# SteppyMk2.net
KiCad netlist of a schematic drawn in EAGLE
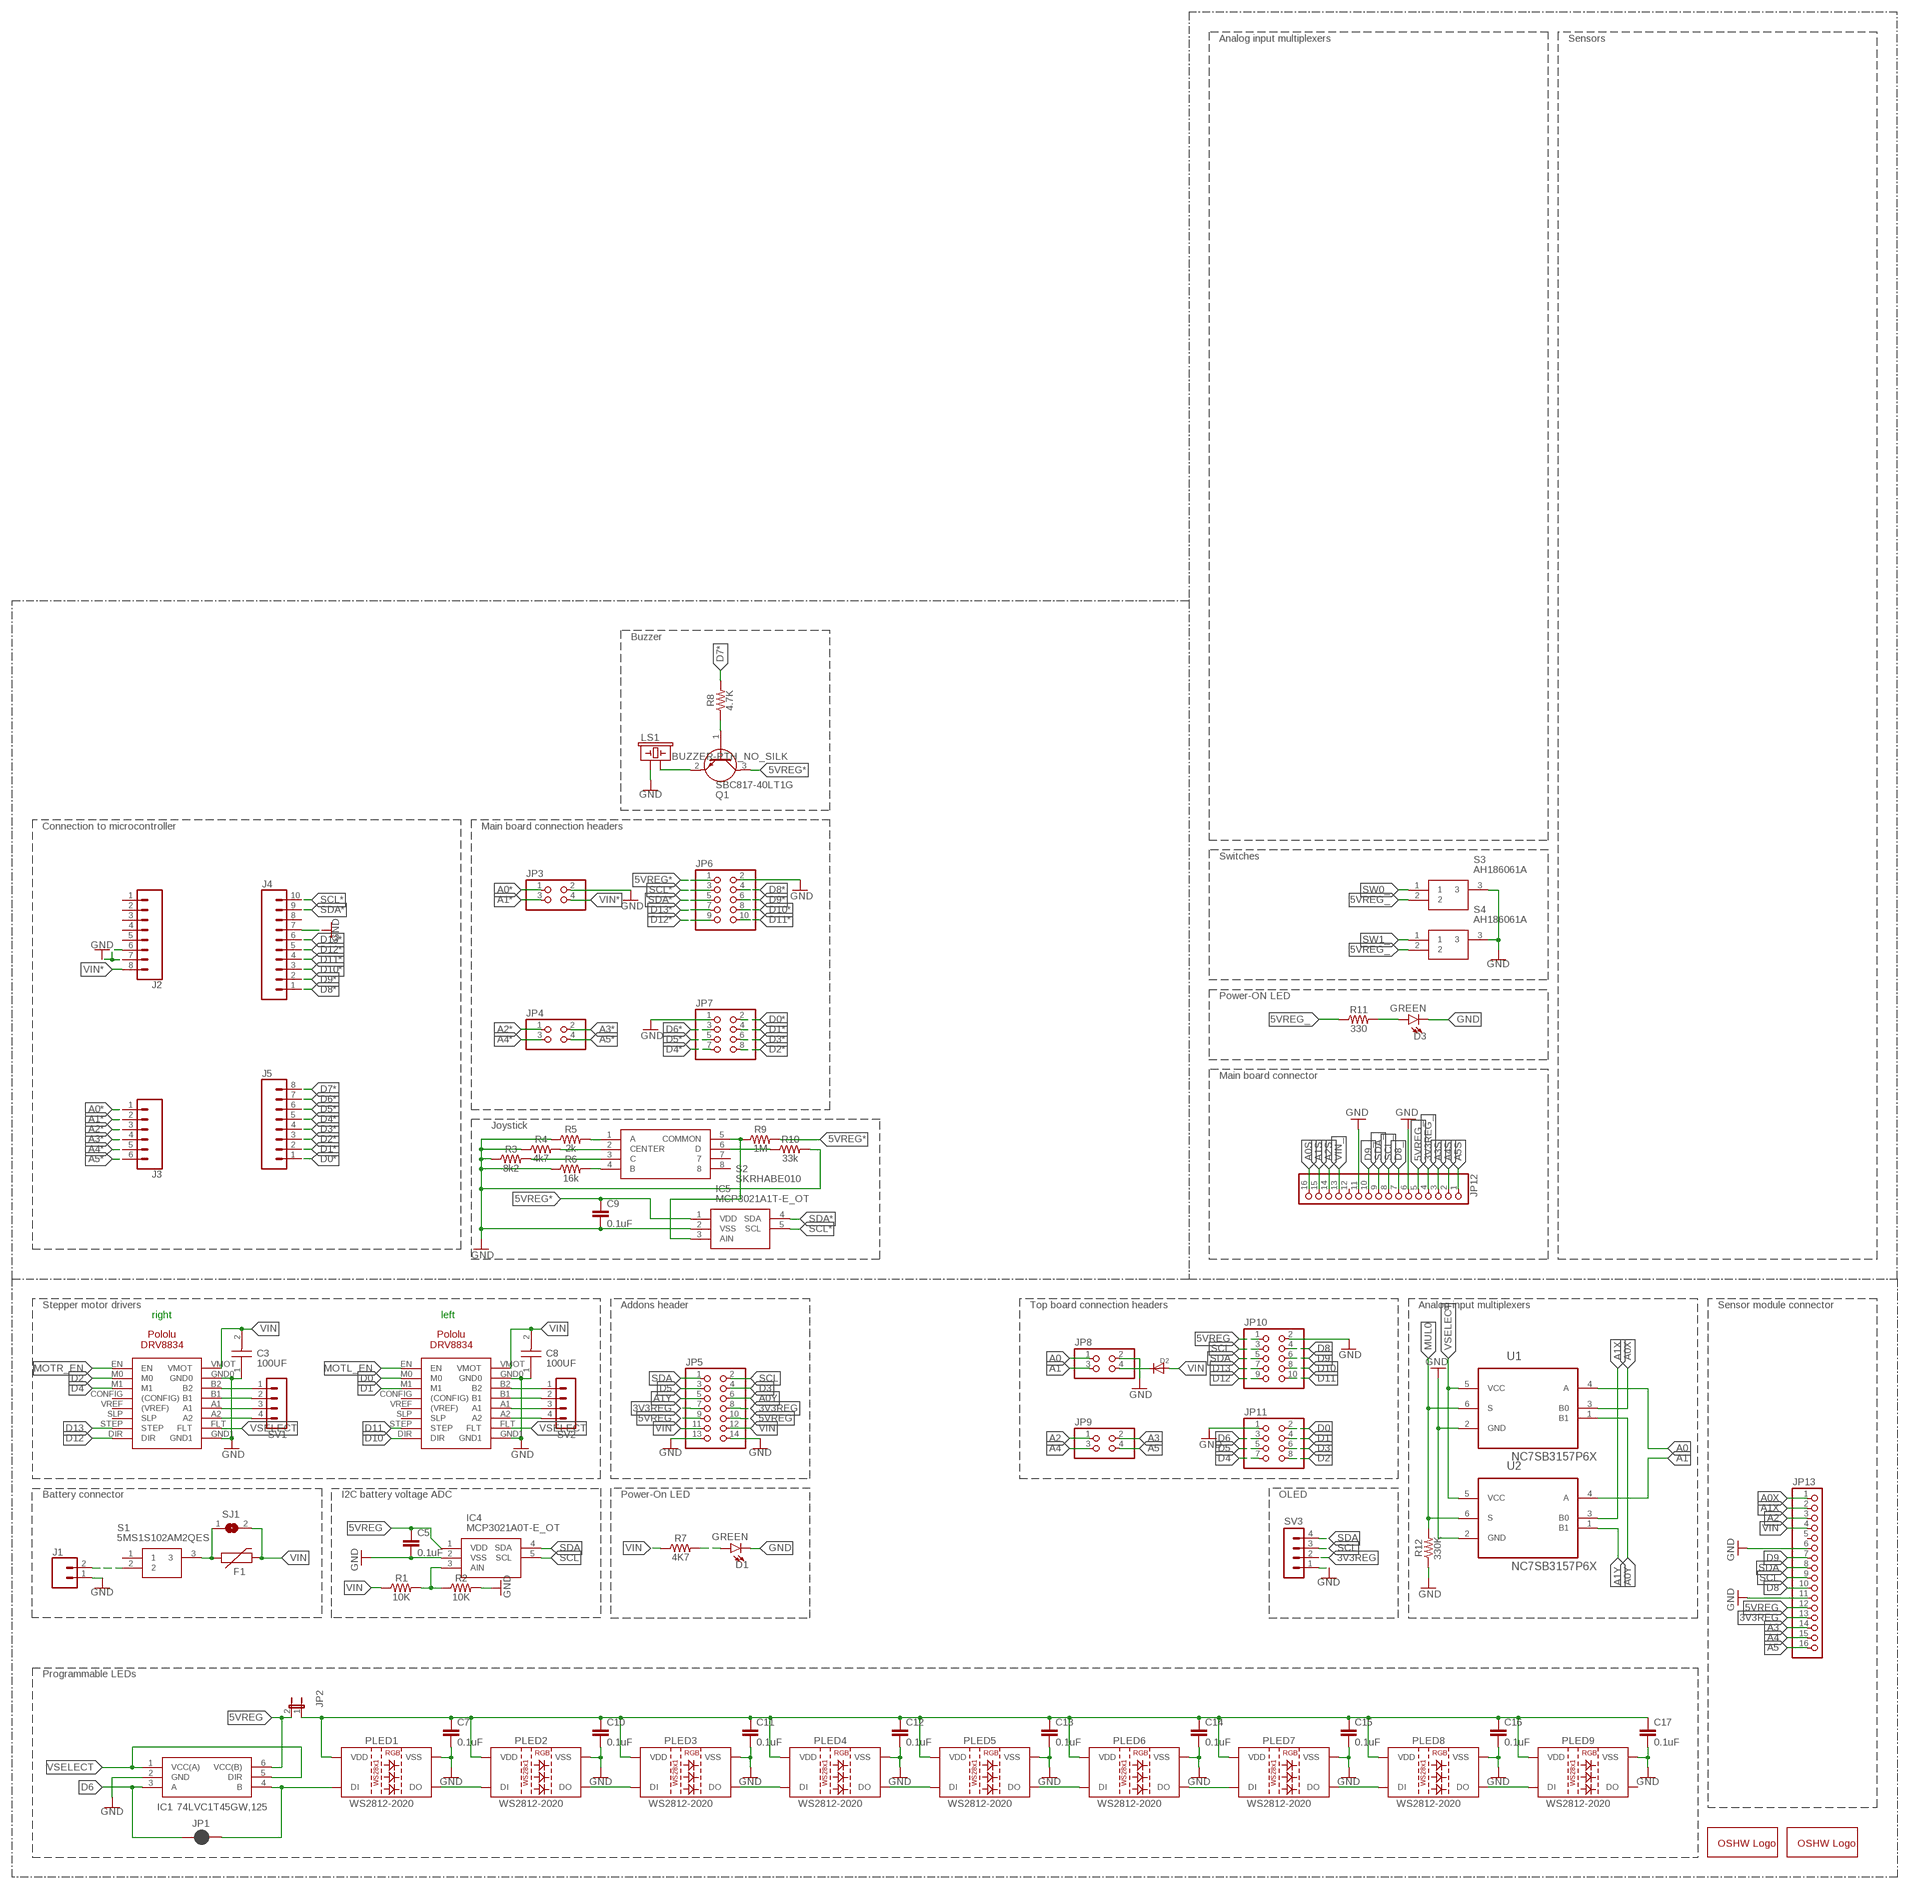
[diagram p0: schematic, sheet 1, part 1 of 3]
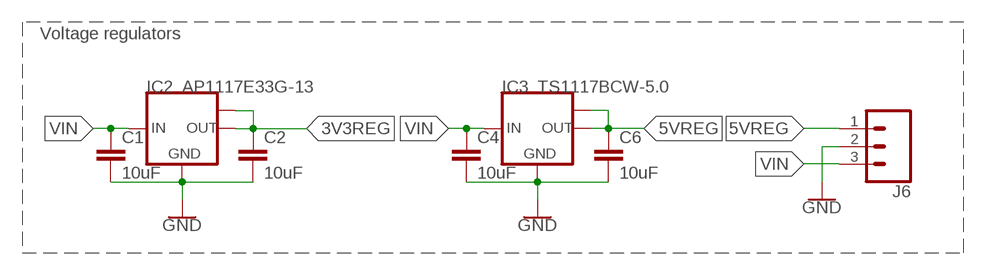
[diagram p1: schematic, sheet 1, part 2 of 3]
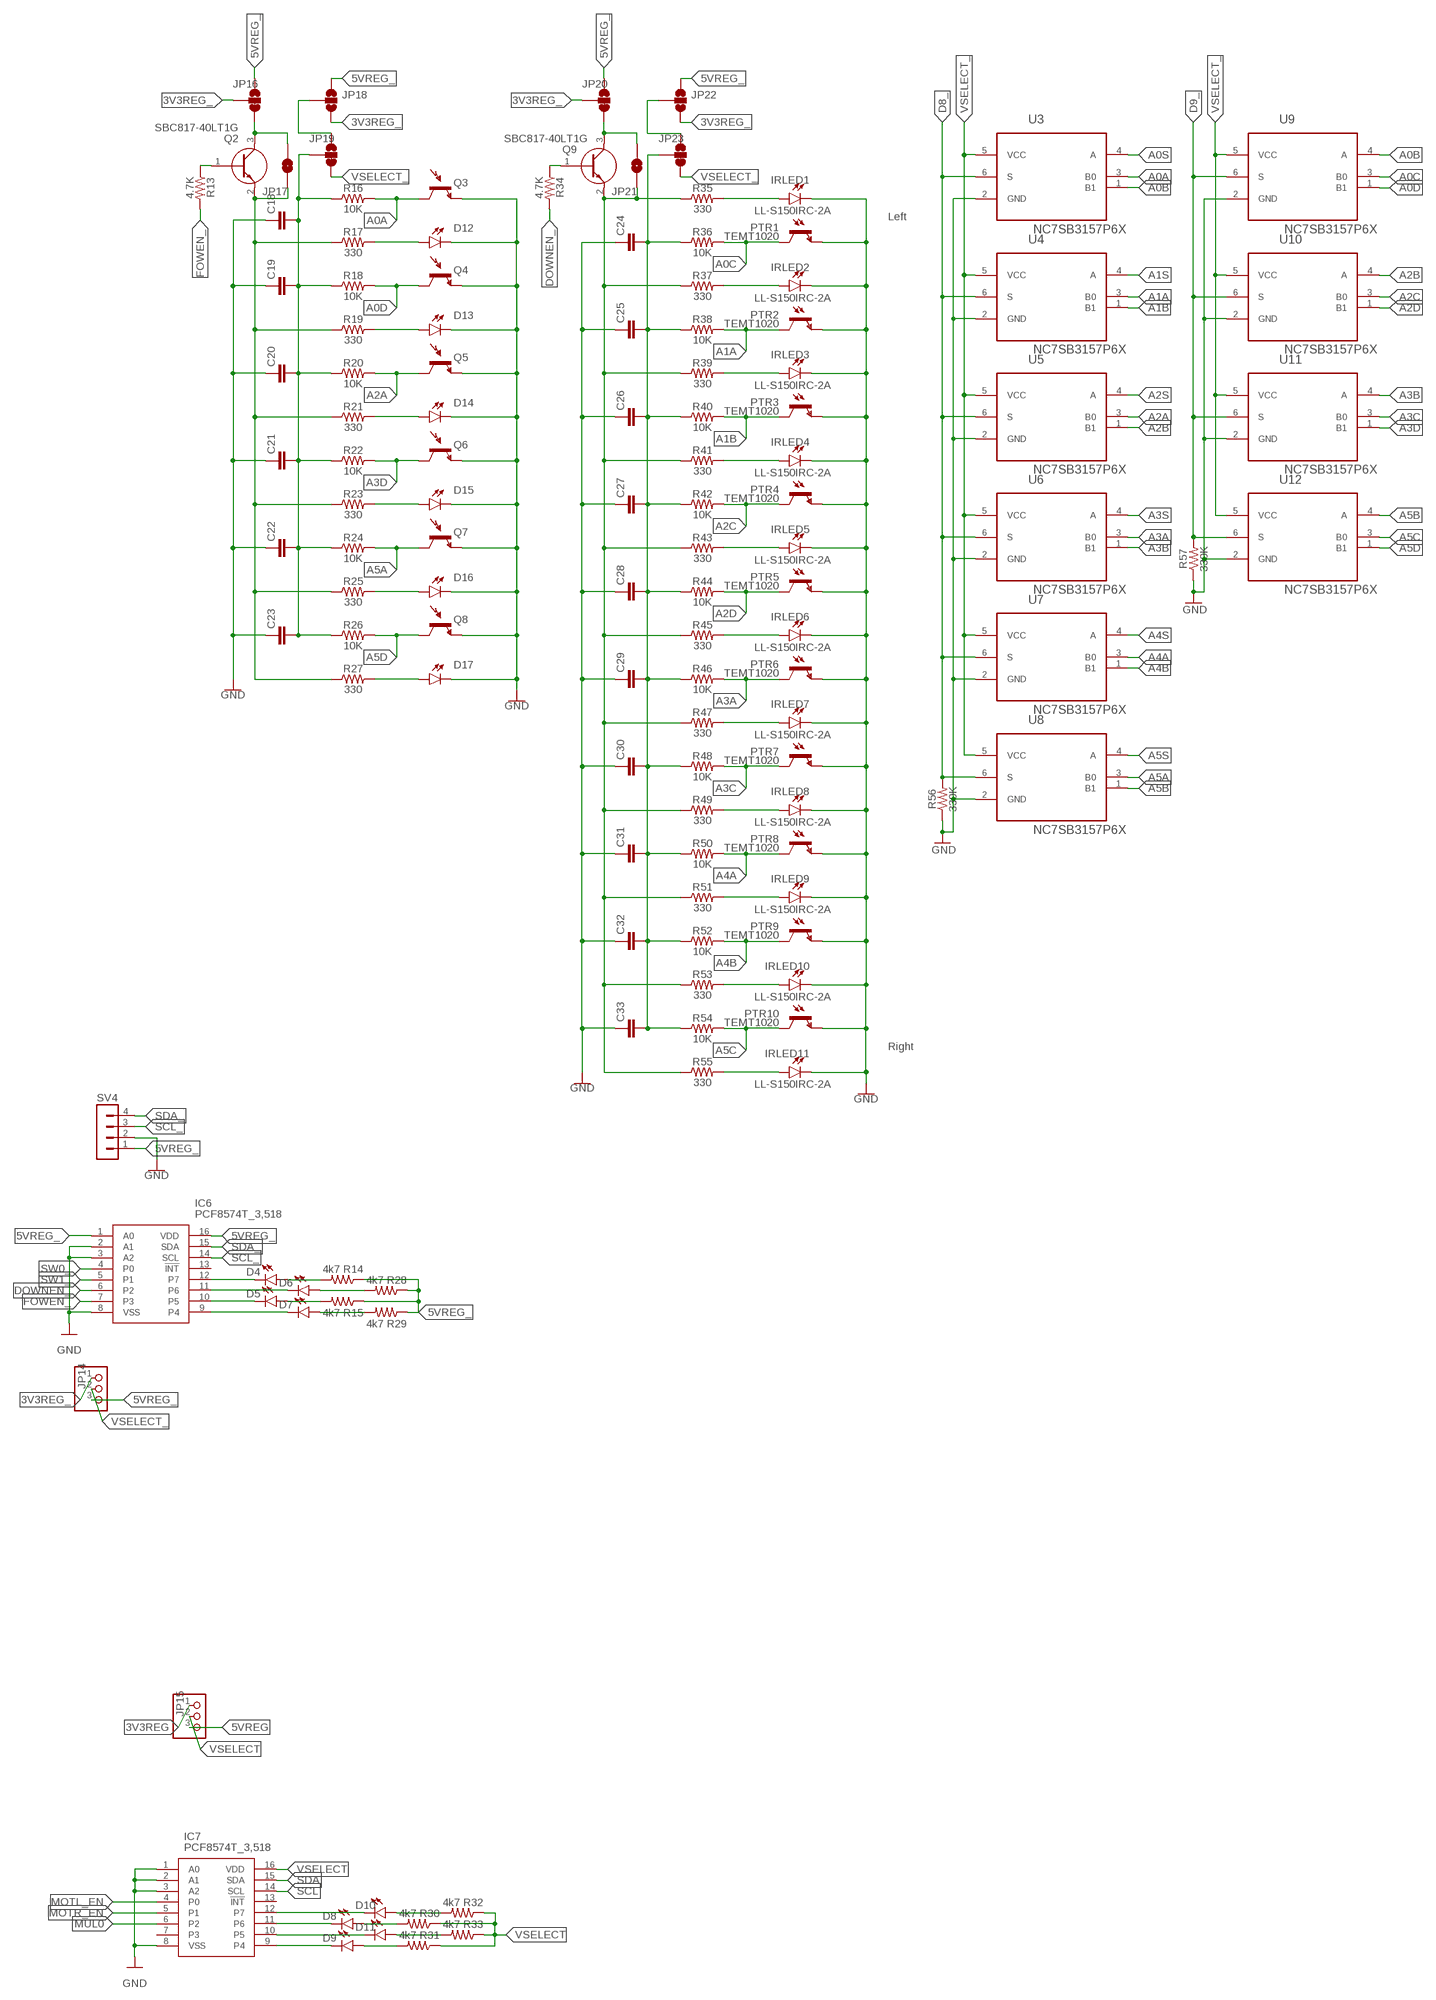
[diagram p2: schematic, sheet 1, part 3 of 3]

(export (version "E")
  (design (tool "Eeschema 10.0.6"))
  (components
    (comp (ref "C1")
      (value "10uF")
      (footprint "eagle-import:0805")
      (libsource (lib "eagle-import") (part "10UF-0805-10V-10%"))
    )
    (comp (ref "C2")
      (value "10uF")
      (footprint "eagle-import:0805")
      (libsource (lib "eagle-import") (part "10UF-0805-10V-10%"))
    )
    (comp (ref "C3")
      (value "100UF")
      (footprint "eagle-import:CAPM7058X610N")
      (fields
        (field (name "MANUFACTURER_PART_NUMBER") "EEEFK1C101P")
        (field (name "RS_PART_NUMBER") "5370433P")
      )
      (libsource (lib "eagle-import") (part "EEEFK1C101P"))
    )
    (comp (ref "C4")
      (value "10uF")
      (footprint "eagle-import:0805")
      (libsource (lib "eagle-import") (part "10UF-0805-10V-10%"))
    )
    (comp (ref "C5")
      (value "0.1uF")
      (footprint "eagle-import:0603")
      (libsource (lib "eagle-import") (part "0.1UF-0603-25V-5%"))
    )
    (comp (ref "C6")
      (value "10uF")
      (footprint "eagle-import:0805")
      (libsource (lib "eagle-import") (part "10UF-0805-10V-10%"))
    )
    (comp (ref "C7")
      (value "0.1uF")
      (footprint "eagle-import:C0805")
      (libsource (lib "eagle-import") (part "C-EUC0805"))
    )
    (comp (ref "C8")
      (value "100UF")
      (footprint "eagle-import:CAPM7058X610N")
      (fields
        (field (name "MANUFACTURER_PART_NUMBER") "EEEFK1C101P")
        (field (name "RS_PART_NUMBER") "5370433P")
      )
      (libsource (lib "eagle-import") (part "EEEFK1C101P"))
    )
    (comp (ref "C9")
      (value "0.1uF")
      (footprint "eagle-import:C0805")
      (libsource (lib "eagle-import") (part "C-EUC0805"))
    )
    (comp (ref "C10")
      (value "0.1uF")
      (footprint "eagle-import:C0805")
      (libsource (lib "eagle-import") (part "C-EUC0805"))
    )
    (comp (ref "C11")
      (value "0.1uF")
      (footprint "eagle-import:C0805")
      (libsource (lib "eagle-import") (part "C-EUC0805"))
    )
    (comp (ref "C12")
      (value "0.1uF")
      (footprint "eagle-import:C0805")
      (libsource (lib "eagle-import") (part "C-EUC0805"))
    )
    (comp (ref "C13")
      (value "0.1uF")
      (footprint "eagle-import:C0805")
      (libsource (lib "eagle-import") (part "C-EUC0805"))
    )
    (comp (ref "C14")
      (value "0.1uF")
      (footprint "eagle-import:C0805")
      (libsource (lib "eagle-import") (part "C-EUC0805"))
    )
    (comp (ref "C15")
      (value "0.1uF")
      (footprint "eagle-import:C0805")
      (libsource (lib "eagle-import") (part "C-EUC0805"))
    )
    (comp (ref "C16")
      (value "0.1uF")
      (footprint "eagle-import:C0805")
      (libsource (lib "eagle-import") (part "C-EUC0805"))
    )
    (comp (ref "C17")
      (value "0.1uF")
      (footprint "eagle-import:C0805")
      (libsource (lib "eagle-import") (part "C-EUC0805"))
    )
    (comp (ref "C18")
      (value "C-EUC0805")
      (footprint "eagle-import:C0805")
      (libsource (lib "eagle-import") (part "C-EUC0805"))
    )
    (comp (ref "C19")
      (value "C-EUC0805")
      (footprint "eagle-import:C0805")
      (libsource (lib "eagle-import") (part "C-EUC0805"))
    )
    (comp (ref "C20")
      (value "C-EUC0805")
      (footprint "eagle-import:C0805")
      (libsource (lib "eagle-import") (part "C-EUC0805"))
    )
    (comp (ref "C21")
      (value "C-EUC0805")
      (footprint "eagle-import:C0805")
      (libsource (lib "eagle-import") (part "C-EUC0805"))
    )
    (comp (ref "C22")
      (value "C-EUC0805")
      (footprint "eagle-import:C0805")
      (libsource (lib "eagle-import") (part "C-EUC0805"))
    )
    (comp (ref "C23")
      (value "C-EUC0805")
      (footprint "eagle-import:C0805")
      (libsource (lib "eagle-import") (part "C-EUC0805"))
    )
    (comp (ref "C24")
      (value "C-EUC0805")
      (footprint "eagle-import:C0805")
      (libsource (lib "eagle-import") (part "C-EUC0805"))
    )
    (comp (ref "C25")
      (value "C-EUC0805")
      (footprint "eagle-import:C0805")
      (libsource (lib "eagle-import") (part "C-EUC0805"))
    )
    (comp (ref "C26")
      (value "C-EUC0805")
      (footprint "eagle-import:C0805")
      (libsource (lib "eagle-import") (part "C-EUC0805"))
    )
    (comp (ref "C27")
      (value "C-EUC0805")
      (footprint "eagle-import:C0805")
      (libsource (lib "eagle-import") (part "C-EUC0805"))
    )
    (comp (ref "C28")
      (value "C-EUC0805")
      (footprint "eagle-import:C0805")
      (libsource (lib "eagle-import") (part "C-EUC0805"))
    )
    (comp (ref "C29")
      (value "C-EUC0805")
      (footprint "eagle-import:C0805")
      (libsource (lib "eagle-import") (part "C-EUC0805"))
    )
    (comp (ref "C30")
      (value "C-EUC0805")
      (footprint "eagle-import:C0805")
      (libsource (lib "eagle-import") (part "C-EUC0805"))
    )
    (comp (ref "C31")
      (value "C-EUC0805")
      (footprint "eagle-import:C0805")
      (libsource (lib "eagle-import") (part "C-EUC0805"))
    )
    (comp (ref "C32")
      (value "C-EUC0805")
      (footprint "eagle-import:C0805")
      (libsource (lib "eagle-import") (part "C-EUC0805"))
    )
    (comp (ref "C33")
      (value "C-EUC0805")
      (footprint "eagle-import:C0805")
      (libsource (lib "eagle-import") (part "C-EUC0805"))
    )
    (comp (ref "D1")
      (value "GREEN")
      (footprint "eagle-import:LED-1206")
      (libsource (lib "eagle-import") (part "LED-GREEN1206"))
    )
    (comp (ref "D2")
      (value "DIODESMA")
      (footprint "eagle-import:SMADIODE")
      (libsource (lib "eagle-import") (part "DIODESMA"))
    )
    (comp (ref "D3")
      (value "GREEN")
      (footprint "eagle-import:LED-1206")
      (libsource (lib "eagle-import") (part "LED-GREEN1206"))
    )
    (comp (ref "D4")
      (value "GREEN")
      (footprint "eagle-import:LED-1206")
      (libsource (lib "eagle-import") (part "LED-GREEN1206"))
    )
    (comp (ref "D5")
      (value "GREEN")
      (footprint "eagle-import:LED-1206")
      (libsource (lib "eagle-import") (part "LED-GREEN1206"))
    )
    (comp (ref "D6")
      (value "GREEN")
      (footprint "eagle-import:LED-1206")
      (libsource (lib "eagle-import") (part "LED-GREEN1206"))
    )
    (comp (ref "D7")
      (value "GREEN")
      (footprint "eagle-import:LED-1206")
      (libsource (lib "eagle-import") (part "LED-GREEN1206"))
    )
    (comp (ref "D8")
      (value "GREEN")
      (footprint "eagle-import:LED-1206")
      (libsource (lib "eagle-import") (part "LED-GREEN1206"))
    )
    (comp (ref "D9")
      (value "GREEN")
      (footprint "eagle-import:LED-1206")
      (libsource (lib "eagle-import") (part "LED-GREEN1206"))
    )
    (comp (ref "D10")
      (value "GREEN")
      (footprint "eagle-import:LED-1206")
      (libsource (lib "eagle-import") (part "LED-GREEN1206"))
    )
    (comp (ref "D11")
      (value "GREEN")
      (footprint "eagle-import:LED-1206")
      (libsource (lib "eagle-import") (part "LED-GREEN1206"))
    )
    (comp (ref "D12")
      (value "LED-IRSIDE_EMITTER")
      (footprint "eagle-import:LTE-302")
      (libsource (lib "eagle-import") (part "LED-IRSIDE_EMITTER"))
    )
    (comp (ref "D13")
      (value "LED-IRSIDE_EMITTER")
      (footprint "eagle-import:LTE-302")
      (libsource (lib "eagle-import") (part "LED-IRSIDE_EMITTER"))
    )
    (comp (ref "D14")
      (value "LED-IRSIDE_EMITTER")
      (footprint "eagle-import:LTE-302")
      (libsource (lib "eagle-import") (part "LED-IRSIDE_EMITTER"))
    )
    (comp (ref "D15")
      (value "LED-IRSIDE_EMITTER")
      (footprint "eagle-import:LTE-302")
      (libsource (lib "eagle-import") (part "LED-IRSIDE_EMITTER"))
    )
    (comp (ref "D16")
      (value "LED-IRSIDE_EMITTER")
      (footprint "eagle-import:LTE-302")
      (libsource (lib "eagle-import") (part "LED-IRSIDE_EMITTER"))
    )
    (comp (ref "D17")
      (value "LED-IRSIDE_EMITTER")
      (footprint "eagle-import:LTE-302")
      (libsource (lib "eagle-import") (part "LED-IRSIDE_EMITTER"))
    )
    (comp (ref "DRV1")
      (value "POLOLU-DRV8825")
      (footprint "eagle-import:POLOLU-DRV8825")
      (libsource (lib "eagle-import") (part "POLOLU-DRV8825"))
    )
    (comp (ref "DRV2")
      (value "POLOLU-DRV8825")
      (footprint "eagle-import:POLOLU-DRV8825")
      (libsource (lib "eagle-import") (part "POLOLU-DRV8825"))
    )
    (comp (ref "F1")
      (value "PPTC_PTH")
      (footprint "eagle-import:PTH")
      (libsource (lib "eagle-import") (part "PPTC_PTH"))
    )
    (comp (ref "GOLD_ORB_SM1")
      (value "OSHWLOGOLOGO8MM")
      (footprint "eagle-import:OSHW_8MM")
      (libsource (lib "eagle-import") (part "OSHWLOGOLOGO8MM"))
    )
    (comp (ref "GOLD_ORB_SM2")
      (value "OSHWLOGOLOGO5MM")
      (footprint "eagle-import:OSHW_5MM")
      (libsource (lib "eagle-import") (part "OSHWLOGOLOGO5MM"))
    )
    (comp (ref "IC1")
      (value "74LVC1T45GW,125")
      (footprint "eagle-import:SOT65P210X110-6N")
      (fields
        (field (name "MOUSER_PART_NUMBER") "771-74LVC1T45GW125")
        (field (name "RS_PART_NUMBER") "8168791P")
      )
      (libsource (lib "eagle-import") (part "74LVC1T45GW,125"))
    )
    (comp (ref "IC2")
      (value "AP1117E33G-13")
      (footprint "eagle-import:SOT223")
      (libsource (lib "eagle-import") (part "LM1117IMPX-3.3"))
    )
    (comp (ref "IC3")
      (value "TS1117BCW-5.0")
      (footprint "eagle-import:SOT223")
      (libsource (lib "eagle-import") (part "LM1117IMPX-5.0"))
    )
    (comp (ref "IC4")
      (value "MCP3021A0T-E_OT")
      (footprint "eagle-import:SOT95P280X145-5N")
      (fields
        (field (name "MANUFACTURER_PART_NUMBER") "MCP3021A0T-E/OT")
        (field (name "MOUSER_PART_NUMBER") "579-MCP3021A0T-E/OT")
      )
      (libsource (lib "eagle-import") (part "MCP3021A0T-E_OT"))
    )
    (comp (ref "IC5")
      (value "MCP3021A1T-E_OT")
      (footprint "eagle-import:SOT95P280X145-5N")
      (fields
        (field (name "MANUFACTURER_PART_NUMBER") "MCP3021A0T-E/OT")
        (field (name "MOUSER_PART_NUMBER") "579-MCP3021A0T-E/OT")
      )
      (libsource (lib "eagle-import") (part "MCP3021A0T-E_OT"))
    )
    (comp (ref "IC6")
      (value "PCF8574T_3,518")
      (footprint "eagle-import:SOIC127P1032X265-16N")
      (fields
        (field (name "MANUFACTURER_PART_NUMBER") "PCF8574T/3,518")
        (field (name "MOUSER_PART_NUMBER") "771-PCF8574TD-T")
      )
      (libsource (lib "eagle-import") (part "PCF8574T_3,518"))
    )
    (comp (ref "IC7")
      (value "PCF8574T_3,518")
      (footprint "eagle-import:SOIC127P1032X265-16N")
      (fields
        (field (name "MANUFACTURER_PART_NUMBER") "PCF8574T/3,518")
        (field (name "MOUSER_PART_NUMBER") "771-PCF8574TD-T")
      )
      (libsource (lib "eagle-import") (part "PCF8574T_3,518"))
    )
    (comp (ref "IRLED1")
      (value "LL-S150IRC-2A")
      (footprint "eagle-import:LEDC3215X130N")
      (fields
        (field (name "MANUFACTURER_PART_NUMBER") "PT15-21C/TR8")
        (field (name "MOUSER_PART_NUMBER") "638-PT1521CTR8")
      )
      (libsource (lib "eagle-import") (part "PT15-21C_TR8"))
    )
    (comp (ref "IRLED2")
      (value "LL-S150IRC-2A")
      (footprint "eagle-import:LEDC3215X130N")
      (fields
        (field (name "MANUFACTURER_PART_NUMBER") "PT15-21C/TR8")
        (field (name "MOUSER_PART_NUMBER") "638-PT1521CTR8")
      )
      (libsource (lib "eagle-import") (part "PT15-21C_TR8"))
    )
    (comp (ref "IRLED3")
      (value "LL-S150IRC-2A")
      (footprint "eagle-import:LEDC3215X130N")
      (fields
        (field (name "MANUFACTURER_PART_NUMBER") "PT15-21C/TR8")
        (field (name "MOUSER_PART_NUMBER") "638-PT1521CTR8")
      )
      (libsource (lib "eagle-import") (part "PT15-21C_TR8"))
    )
    (comp (ref "IRLED4")
      (value "LL-S150IRC-2A")
      (footprint "eagle-import:LEDC3215X130N")
      (fields
        (field (name "MANUFACTURER_PART_NUMBER") "PT15-21C/TR8")
        (field (name "MOUSER_PART_NUMBER") "638-PT1521CTR8")
      )
      (libsource (lib "eagle-import") (part "PT15-21C_TR8"))
    )
    (comp (ref "IRLED5")
      (value "LL-S150IRC-2A")
      (footprint "eagle-import:LEDC3215X130N")
      (fields
        (field (name "MANUFACTURER_PART_NUMBER") "PT15-21C/TR8")
        (field (name "MOUSER_PART_NUMBER") "638-PT1521CTR8")
      )
      (libsource (lib "eagle-import") (part "PT15-21C_TR8"))
    )
    (comp (ref "IRLED6")
      (value "LL-S150IRC-2A")
      (footprint "eagle-import:LEDC3215X130N")
      (fields
        (field (name "MANUFACTURER_PART_NUMBER") "PT15-21C/TR8")
        (field (name "MOUSER_PART_NUMBER") "638-PT1521CTR8")
      )
      (libsource (lib "eagle-import") (part "PT15-21C_TR8"))
    )
    (comp (ref "IRLED7")
      (value "LL-S150IRC-2A")
      (footprint "eagle-import:LEDC3215X130N")
      (fields
        (field (name "MANUFACTURER_PART_NUMBER") "PT15-21C/TR8")
        (field (name "MOUSER_PART_NUMBER") "638-PT1521CTR8")
      )
      (libsource (lib "eagle-import") (part "PT15-21C_TR8"))
    )
    (comp (ref "IRLED8")
      (value "LL-S150IRC-2A")
      (footprint "eagle-import:LEDC3215X130N")
      (fields
        (field (name "MANUFACTURER_PART_NUMBER") "PT15-21C/TR8")
        (field (name "MOUSER_PART_NUMBER") "638-PT1521CTR8")
      )
      (libsource (lib "eagle-import") (part "PT15-21C_TR8"))
    )
    (comp (ref "IRLED9")
      (value "LL-S150IRC-2A")
      (footprint "eagle-import:LEDC3215X130N")
      (fields
        (field (name "MANUFACTURER_PART_NUMBER") "PT15-21C/TR8")
        (field (name "MOUSER_PART_NUMBER") "638-PT1521CTR8")
      )
      (libsource (lib "eagle-import") (part "PT15-21C_TR8"))
    )
    (comp (ref "IRLED10")
      (value "LL-S150IRC-2A")
      (footprint "eagle-import:LEDC3215X130N")
      (fields
        (field (name "MANUFACTURER_PART_NUMBER") "PT15-21C/TR8")
        (field (name "MOUSER_PART_NUMBER") "638-PT1521CTR8")
      )
      (libsource (lib "eagle-import") (part "PT15-21C_TR8"))
    )
    (comp (ref "IRLED11")
      (value "LL-S150IRC-2A")
      (footprint "eagle-import:LEDC3215X130N")
      (fields
        (field (name "MANUFACTURER_PART_NUMBER") "PT15-21C/TR8")
        (field (name "MOUSER_PART_NUMBER") "638-PT1521CTR8")
      )
      (libsource (lib "eagle-import") (part "PT15-21C_TR8"))
    )
    (comp (ref "J1")
      (value "CONN_02")
      (footprint "eagle-import:1X02")
      (libsource (lib "eagle-import") (part "CONN_02"))
    )
    (comp (ref "J2")
      (value "CONN_08\"")
      (footprint "eagle-import:1X08")
      (libsource (lib "eagle-import") (part "CONN_08{dblquote}"))
    )
    (comp (ref "J3")
      (value "CONN_06SILK_FEMALE_PTH")
      (footprint "eagle-import:1X06")
      (libsource (lib "eagle-import") (part "CONN_06SILK_FEMALE_PTH"))
    )
    (comp (ref "J4")
      (value "CONN_10\"")
      (footprint "eagle-import:1X10")
      (libsource (lib "eagle-import") (part "CONN_10{dblquote}"))
    )
    (comp (ref "J5")
      (value "CONN_08\"")
      (footprint "eagle-import:1X08")
      (libsource (lib "eagle-import") (part "CONN_08{dblquote}"))
    )
    (comp (ref "J6")
      (value "455-1750-1-ND")
      (footprint "eagle-import:1X03")
      (libsource (lib "eagle-import") (part "CONN_03"))
    )
    (comp (ref "JP1")
      (value "JUMPER-SMT_2_NC_PASTE_SILK")
      (footprint "eagle-import:SMT-JUMPER_2_NC_PASTE_SILK")
      (libsource (lib "eagle-import") (part "JUMPER-SMT_2_NC_PASTE_SILK"))
    )
    (comp (ref "JP2")
      (value "JP1E")
      (footprint "eagle-import:JP1")
      (libsource (lib "eagle-import") (part "JP1E"))
    )
    (comp (ref "JP3")
      (value "PINHD-2X2")
      (footprint "eagle-import:2X02")
      (libsource (lib "eagle-import") (part "PINHD-2X2"))
    )
    (comp (ref "JP4")
      (value "PINHD-2X2")
      (footprint "eagle-import:2X02")
      (libsource (lib "eagle-import") (part "PINHD-2X2"))
    )
    (comp (ref "JP5")
      (value "PINHD-2X7")
      (footprint "eagle-import:2X07")
      (libsource (lib "eagle-import") (part "PINHD-2X7"))
    )
    (comp (ref "JP6")
      (value "PINHD-2X5")
      (footprint "eagle-import:2X05")
      (libsource (lib "eagle-import") (part "PINHD-2X5"))
    )
    (comp (ref "JP7")
      (value "PINHD-2X4")
      (footprint "eagle-import:2X04")
      (libsource (lib "eagle-import") (part "PINHD-2X4"))
    )
    (comp (ref "JP8")
      (value "PINHD-2X2")
      (footprint "eagle-import:2X02")
      (libsource (lib "eagle-import") (part "PINHD-2X2"))
    )
    (comp (ref "JP9")
      (value "PINHD-2X2")
      (footprint "eagle-import:2X02")
      (libsource (lib "eagle-import") (part "PINHD-2X2"))
    )
    (comp (ref "JP10")
      (value "PINHD-2X5")
      (footprint "eagle-import:2X05")
      (libsource (lib "eagle-import") (part "PINHD-2X5"))
    )
    (comp (ref "JP11")
      (value "PINHD-2X4")
      (footprint "eagle-import:2X04")
      (libsource (lib "eagle-import") (part "PINHD-2X4"))
    )
    (comp (ref "JP12")
      (value "PINHD-1X16/90")
      (footprint "eagle-import:1X16_90")
      (libsource (lib "eagle-import") (part "PINHD-1X16/90"))
    )
    (comp (ref "JP13")
      (value "PINHD-1X16")
      (footprint "eagle-import:1X16")
      (libsource (lib "eagle-import") (part "PINHD-1X16"))
    )
    (comp (ref "JP14")
      (value "PINHD-1X3")
      (footprint "eagle-import:1X03")
      (libsource (lib "eagle-import") (part "PINHD-1X3"))
    )
    (comp (ref "JP15")
      (value "PINHD-1X3")
      (footprint "eagle-import:1X03")
      (libsource (lib "eagle-import") (part "PINHD-1X3"))
    )
    (comp (ref "JP16")
      (value "JUMPER-SMT_3_1-NC_TRACE_NO-SILK")
      (footprint "eagle-import:SMT-JUMPER_3_1-NC_TRACE_NO-SILK")
      (libsource (lib "eagle-import") (part "JUMPER-SMT_3_1-NC_TRACE_NO-SILK"))
    )
    (comp (ref "JP17")
      (value "JUMPER-SMT_2_NO_NO-SILK")
      (footprint "eagle-import:SMT-JUMPER_2_NO_NO-SILK")
      (libsource (lib "eagle-import") (part "JUMPER-SMT_2_NO_NO-SILK"))
    )
    (comp (ref "JP18")
      (value "JUMPER-SMT_3_NO_NO_SILK")
      (footprint "eagle-import:SMT-JUMPER_3_0-NO_TRACE_NO-SILK")
      (libsource (lib "eagle-import") (part "JUMPER-SMT_3_NO_NO_SILK"))
    )
    (comp (ref "JP19")
      (value "JUMPER-SMT_3_1-NC_TRACE_NO-SILK")
      (footprint "eagle-import:SMT-JUMPER_3_1-NC_TRACE_NO-SILK")
      (libsource (lib "eagle-import") (part "JUMPER-SMT_3_1-NC_TRACE_NO-SILK"))
    )
    (comp (ref "JP20")
      (value "JUMPER-SMT_3_1-NC_TRACE_NO-SILK")
      (footprint "eagle-import:SMT-JUMPER_3_1-NC_TRACE_NO-SILK")
      (libsource (lib "eagle-import") (part "JUMPER-SMT_3_1-NC_TRACE_NO-SILK"))
    )
    (comp (ref "JP21")
      (value "JUMPER-SMT_2_NO_NO-SILK")
      (footprint "eagle-import:SMT-JUMPER_2_NO_NO-SILK")
      (libsource (lib "eagle-import") (part "JUMPER-SMT_2_NO_NO-SILK"))
    )
    (comp (ref "JP22")
      (value "JUMPER-SMT_3_NO_NO_SILK")
      (footprint "eagle-import:SMT-JUMPER_3_0-NO_TRACE_NO-SILK")
      (libsource (lib "eagle-import") (part "JUMPER-SMT_3_NO_NO_SILK"))
    )
    (comp (ref "JP23")
      (value "JUMPER-SMT_3_1-NC_TRACE_NO-SILK")
      (footprint "eagle-import:SMT-JUMPER_3_1-NC_TRACE_NO-SILK")
      (libsource (lib "eagle-import") (part "JUMPER-SMT_3_1-NC_TRACE_NO-SILK"))
    )
    (comp (ref "LS1")
      (value "BUZZER-PTH_NO_SILK")
      (footprint "eagle-import:BUZZER-12MM-NS")
      (libsource (lib "eagle-import") (part "BUZZER-PTH_NO_SILK"))
    )
    (comp (ref "PLED1")
      (value "WS2812-2020")
      (footprint "eagle-import:WS2812-2020")
      (libsource (lib "eagle-import") (part "WS2812-2020"))
    )
    (comp (ref "PLED2")
      (value "WS2812-2020")
      (footprint "eagle-import:WS2812-2020")
      (libsource (lib "eagle-import") (part "WS2812-2020"))
    )
    (comp (ref "PLED3")
      (value "WS2812-2020")
      (footprint "eagle-import:WS2812-2020")
      (libsource (lib "eagle-import") (part "WS2812-2020"))
    )
    (comp (ref "PLED4")
      (value "WS2812-2020")
      (footprint "eagle-import:WS2812-2020")
      (libsource (lib "eagle-import") (part "WS2812-2020"))
    )
    (comp (ref "PLED5")
      (value "WS2812-2020")
      (footprint "eagle-import:WS2812-2020")
      (libsource (lib "eagle-import") (part "WS2812-2020"))
    )
    (comp (ref "PLED6")
      (value "WS2812-2020")
      (footprint "eagle-import:WS2812-2020")
      (libsource (lib "eagle-import") (part "WS2812-2020"))
    )
    (comp (ref "PLED7")
      (value "WS2812-2020")
      (footprint "eagle-import:WS2812-2020")
      (libsource (lib "eagle-import") (part "WS2812-2020"))
    )
    (comp (ref "PLED8")
      (value "WS2812-2020")
      (footprint "eagle-import:WS2812-2020")
      (libsource (lib "eagle-import") (part "WS2812-2020"))
    )
    (comp (ref "PLED9")
      (value "WS2812-2020")
      (footprint "eagle-import:WS2812-2020")
      (libsource (lib "eagle-import") (part "WS2812-2020"))
    )
    (comp (ref "PTR1")
      (value "TEMT1020")
      (footprint "eagle-import:TEMT1020")
      (fields
        (field (name "MANUFACTURER_PART_NUMBER") "TEMD1020")
        (field (name "MOUSER_PART_NUMBER") "782-TEMD1020")
        (field (name "RS_PART_NUMBER") "1808105P")
      )
      (libsource (lib "eagle-import") (part "TEMT1020"))
    )
    (comp (ref "PTR2")
      (value "TEMT1020")
      (footprint "eagle-import:TEMT1020")
      (fields
        (field (name "MANUFACTURER_PART_NUMBER") "TEMD1020")
        (field (name "MOUSER_PART_NUMBER") "782-TEMD1020")
        (field (name "RS_PART_NUMBER") "1808105P")
      )
      (libsource (lib "eagle-import") (part "TEMT1020"))
    )
    (comp (ref "PTR3")
      (value "TEMT1020")
      (footprint "eagle-import:TEMT1020")
      (fields
        (field (name "MANUFACTURER_PART_NUMBER") "TEMD1020")
        (field (name "MOUSER_PART_NUMBER") "782-TEMD1020")
        (field (name "RS_PART_NUMBER") "1808105P")
      )
      (libsource (lib "eagle-import") (part "TEMT1020"))
    )
    (comp (ref "PTR4")
      (value "TEMT1020")
      (footprint "eagle-import:TEMT1020")
      (fields
        (field (name "MANUFACTURER_PART_NUMBER") "TEMD1020")
        (field (name "MOUSER_PART_NUMBER") "782-TEMD1020")
        (field (name "RS_PART_NUMBER") "1808105P")
      )
      (libsource (lib "eagle-import") (part "TEMT1020"))
    )
    (comp (ref "PTR5")
      (value "TEMT1020")
      (footprint "eagle-import:TEMT1020")
      (fields
        (field (name "MANUFACTURER_PART_NUMBER") "TEMD1020")
        (field (name "MOUSER_PART_NUMBER") "782-TEMD1020")
        (field (name "RS_PART_NUMBER") "1808105P")
      )
      (libsource (lib "eagle-import") (part "TEMT1020"))
    )
    (comp (ref "PTR6")
      (value "TEMT1020")
      (footprint "eagle-import:TEMT1020")
      (fields
        (field (name "MANUFACTURER_PART_NUMBER") "TEMD1020")
        (field (name "MOUSER_PART_NUMBER") "782-TEMD1020")
        (field (name "RS_PART_NUMBER") "1808105P")
      )
      (libsource (lib "eagle-import") (part "TEMT1020"))
    )
    (comp (ref "PTR7")
      (value "TEMT1020")
      (footprint "eagle-import:TEMT1020")
      (fields
        (field (name "MANUFACTURER_PART_NUMBER") "TEMD1020")
        (field (name "MOUSER_PART_NUMBER") "782-TEMD1020")
        (field (name "RS_PART_NUMBER") "1808105P")
      )
      (libsource (lib "eagle-import") (part "TEMT1020"))
    )
    (comp (ref "PTR8")
      (value "TEMT1020")
      (footprint "eagle-import:TEMT1020")
      (fields
        (field (name "MANUFACTURER_PART_NUMBER") "TEMD1020")
        (field (name "MOUSER_PART_NUMBER") "782-TEMD1020")
        (field (name "RS_PART_NUMBER") "1808105P")
      )
      (libsource (lib "eagle-import") (part "TEMT1020"))
    )
    (comp (ref "PTR9")
      (value "TEMT1020")
      (footprint "eagle-import:TEMT1020")
      (fields
        (field (name "MANUFACTURER_PART_NUMBER") "TEMD1020")
        (field (name "MOUSER_PART_NUMBER") "782-TEMD1020")
        (field (name "RS_PART_NUMBER") "1808105P")
      )
      (libsource (lib "eagle-import") (part "TEMT1020"))
    )
    (comp (ref "PTR10")
      (value "TEMT1020")
      (footprint "eagle-import:TEMT1020")
      (fields
        (field (name "MANUFACTURER_PART_NUMBER") "TEMD1020")
        (field (name "MOUSER_PART_NUMBER") "782-TEMD1020")
        (field (name "RS_PART_NUMBER") "1808105P")
      )
      (libsource (lib "eagle-import") (part "TEMT1020"))
    )
    (comp (ref "Q1")
      (value "SBC817-40LT1G")
      (footprint "eagle-import:SOT96P237X111-3N")
      (fields
        (field (name "MOUSER_PART_NUMBER") "863-SBC817-40LT1G")
        (field (name "RS_PART_NUMBER") "1631159")
      )
      (libsource (lib "eagle-import") (part "SBC817-40LT1G"))
    )
    (comp (ref "Q2")
      (value "SBC817-40LT1G")
      (footprint "eagle-import:SOT96P237X111-3N")
      (fields
        (field (name "MOUSER_PART_NUMBER") "863-SBC817-40LT1G")
        (field (name "RS_PART_NUMBER") "1631159")
      )
      (libsource (lib "eagle-import") (part "SBC817-40LT1G"))
    )
    (comp (ref "Q3")
      (value "LTR-301")
      (footprint "eagle-import:LTR-301")
      (libsource (lib "eagle-import") (part "LTR-301"))
    )
    (comp (ref "Q4")
      (value "LTR-301")
      (footprint "eagle-import:LTR-301")
      (libsource (lib "eagle-import") (part "LTR-301"))
    )
    (comp (ref "Q5")
      (value "LTR-301")
      (footprint "eagle-import:LTR-301")
      (libsource (lib "eagle-import") (part "LTR-301"))
    )
    (comp (ref "Q6")
      (value "LTR-301")
      (footprint "eagle-import:LTR-301")
      (libsource (lib "eagle-import") (part "LTR-301"))
    )
    (comp (ref "Q7")
      (value "LTR-301")
      (footprint "eagle-import:LTR-301")
      (libsource (lib "eagle-import") (part "LTR-301"))
    )
    (comp (ref "Q8")
      (value "LTR-301")
      (footprint "eagle-import:LTR-301")
      (libsource (lib "eagle-import") (part "LTR-301"))
    )
    (comp (ref "Q9")
      (value "SBC817-40LT1G")
      (footprint "eagle-import:SOT96P237X111-3N")
      (fields
        (field (name "MOUSER_PART_NUMBER") "863-SBC817-40LT1G")
        (field (name "RS_PART_NUMBER") "1631159")
      )
      (libsource (lib "eagle-import") (part "SBC817-40LT1G"))
    )
    (comp (ref "R1")
      (value "10K")
      (footprint "eagle-import:0805")
      (libsource (lib "eagle-import") (part "RESISTOR0805"))
    )
    (comp (ref "R2")
      (value "10K")
      (footprint "eagle-import:0805")
      (libsource (lib "eagle-import") (part "RESISTOR0805"))
    )
    (comp (ref "R3")
      (value "8k2")
      (footprint "eagle-import:0805")
      (libsource (lib "eagle-import") (part "RESISTOR0805"))
    )
    (comp (ref "R4")
      (value "4k7")
      (footprint "eagle-import:0805")
      (libsource (lib "eagle-import") (part "RESISTOR0805"))
    )
    (comp (ref "R5")
      (value "2k")
      (footprint "eagle-import:0805")
      (libsource (lib "eagle-import") (part "RESISTOR0805"))
    )
    (comp (ref "R6")
      (value "16k")
      (footprint "eagle-import:0805")
      (libsource (lib "eagle-import") (part "RESISTOR0805"))
    )
    (comp (ref "R7")
      (value "4K7")
      (footprint "eagle-import:0805")
      (libsource (lib "eagle-import") (part "RESISTOR0805"))
    )
    (comp (ref "R8")
      (value "4.7K")
      (footprint "eagle-import:0805")
      (libsource (lib "eagle-import") (part "RESISTOR0805"))
    )
    (comp (ref "R9")
      (value "1M")
      (footprint "eagle-import:0805")
      (libsource (lib "eagle-import") (part "RESISTOR0805"))
    )
    (comp (ref "R10")
      (value "33k")
      (footprint "eagle-import:0805")
      (libsource (lib "eagle-import") (part "RESISTOR0805"))
    )
    (comp (ref "R11")
      (value "330")
      (footprint "eagle-import:0805")
      (libsource (lib "eagle-import") (part "RESISTOR0805"))
    )
    (comp (ref "R12")
      (value "330K")
      (footprint "eagle-import:0805")
      (libsource (lib "eagle-import") (part "RESISTOR0805"))
    )
    (comp (ref "R13")
      (value "4.7K")
      (footprint "eagle-import:0805")
      (libsource (lib "eagle-import") (part "RESISTOR0805"))
    )
    (comp (ref "R14")
      (value "4k7")
      (footprint "eagle-import:0805")
      (libsource (lib "eagle-import") (part "RESISTOR0805"))
    )
    (comp (ref "R15")
      (value "4k7")
      (footprint "eagle-import:0805")
      (libsource (lib "eagle-import") (part "RESISTOR0805"))
    )
    (comp (ref "R16")
      (value "10K")
      (footprint "eagle-import:0805")
      (libsource (lib "eagle-import") (part "RESISTOR0805"))
    )
    (comp (ref "R17")
      (value "330")
      (footprint "eagle-import:0805")
      (libsource (lib "eagle-import") (part "RESISTOR0805"))
    )
    (comp (ref "R18")
      (value "10K")
      (footprint "eagle-import:0805")
      (libsource (lib "eagle-import") (part "RESISTOR0805"))
    )
    (comp (ref "R19")
      (value "330")
      (footprint "eagle-import:0805")
      (libsource (lib "eagle-import") (part "RESISTOR0805"))
    )
    (comp (ref "R20")
      (value "10K")
      (footprint "eagle-import:0805")
      (libsource (lib "eagle-import") (part "RESISTOR0805"))
    )
    (comp (ref "R21")
      (value "330")
      (footprint "eagle-import:0805")
      (libsource (lib "eagle-import") (part "RESISTOR0805"))
    )
    (comp (ref "R22")
      (value "10K")
      (footprint "eagle-import:0805")
      (libsource (lib "eagle-import") (part "RESISTOR0805"))
    )
    (comp (ref "R23")
      (value "330")
      (footprint "eagle-import:0805")
      (libsource (lib "eagle-import") (part "RESISTOR0805"))
    )
    (comp (ref "R24")
      (value "10K")
      (footprint "eagle-import:0805")
      (libsource (lib "eagle-import") (part "RESISTOR0805"))
    )
    (comp (ref "R25")
      (value "330")
      (footprint "eagle-import:0805")
      (libsource (lib "eagle-import") (part "RESISTOR0805"))
    )
    (comp (ref "R26")
      (value "10K")
      (footprint "eagle-import:0805")
      (libsource (lib "eagle-import") (part "RESISTOR0805"))
    )
    (comp (ref "R27")
      (value "330")
      (footprint "eagle-import:0805")
      (libsource (lib "eagle-import") (part "RESISTOR0805"))
    )
    (comp (ref "R28")
      (value "4k7")
      (footprint "eagle-import:0805")
      (libsource (lib "eagle-import") (part "RESISTOR0805"))
    )
    (comp (ref "R29")
      (value "4k7")
      (footprint "eagle-import:0805")
      (libsource (lib "eagle-import") (part "RESISTOR0805"))
    )
    (comp (ref "R30")
      (value "4k7")
      (footprint "eagle-import:0805")
      (libsource (lib "eagle-import") (part "RESISTOR0805"))
    )
    (comp (ref "R31")
      (value "4k7")
      (footprint "eagle-import:0805")
      (libsource (lib "eagle-import") (part "RESISTOR0805"))
    )
    (comp (ref "R32")
      (value "4k7")
      (footprint "eagle-import:0805")
      (libsource (lib "eagle-import") (part "RESISTOR0805"))
    )
    (comp (ref "R33")
      (value "4k7")
      (footprint "eagle-import:0805")
      (libsource (lib "eagle-import") (part "RESISTOR0805"))
    )
    (comp (ref "R34")
      (value "4.7K")
      (footprint "eagle-import:0805")
      (libsource (lib "eagle-import") (part "RESISTOR0805"))
    )
    (comp (ref "R35")
      (value "330")
      (footprint "eagle-import:0805")
      (libsource (lib "eagle-import") (part "RESISTOR0805"))
    )
    (comp (ref "R36")
      (value "10K")
      (footprint "eagle-import:0805")
      (libsource (lib "eagle-import") (part "RESISTOR0805"))
    )
    (comp (ref "R37")
      (value "330")
      (footprint "eagle-import:0805")
      (libsource (lib "eagle-import") (part "RESISTOR0805"))
    )
    (comp (ref "R38")
      (value "10K")
      (footprint "eagle-import:0805")
      (libsource (lib "eagle-import") (part "RESISTOR0805"))
    )
    (comp (ref "R39")
      (value "330")
      (footprint "eagle-import:0805")
      (libsource (lib "eagle-import") (part "RESISTOR0805"))
    )
    (comp (ref "R40")
      (value "10K")
      (footprint "eagle-import:0805")
      (libsource (lib "eagle-import") (part "RESISTOR0805"))
    )
    (comp (ref "R41")
      (value "330")
      (footprint "eagle-import:0805")
      (libsource (lib "eagle-import") (part "RESISTOR0805"))
    )
    (comp (ref "R42")
      (value "10K")
      (footprint "eagle-import:0805")
      (libsource (lib "eagle-import") (part "RESISTOR0805"))
    )
    (comp (ref "R43")
      (value "330")
      (footprint "eagle-import:0805")
      (libsource (lib "eagle-import") (part "RESISTOR0805"))
    )
    (comp (ref "R44")
      (value "10K")
      (footprint "eagle-import:0805")
      (libsource (lib "eagle-import") (part "RESISTOR0805"))
    )
    (comp (ref "R45")
      (value "330")
      (footprint "eagle-import:0805")
      (libsource (lib "eagle-import") (part "RESISTOR0805"))
    )
    (comp (ref "R46")
      (value "10K")
      (footprint "eagle-import:0805")
      (libsource (lib "eagle-import") (part "RESISTOR0805"))
    )
    (comp (ref "R47")
      (value "330")
      (footprint "eagle-import:0805")
      (libsource (lib "eagle-import") (part "RESISTOR0805"))
    )
    (comp (ref "R48")
      (value "10K")
      (footprint "eagle-import:0805")
      (libsource (lib "eagle-import") (part "RESISTOR0805"))
    )
    (comp (ref "R49")
      (value "330")
      (footprint "eagle-import:0805")
      (libsource (lib "eagle-import") (part "RESISTOR0805"))
    )
    (comp (ref "R50")
      (value "10K")
      (footprint "eagle-import:0805")
      (libsource (lib "eagle-import") (part "RESISTOR0805"))
    )
    (comp (ref "R51")
      (value "330")
      (footprint "eagle-import:0805")
      (libsource (lib "eagle-import") (part "RESISTOR0805"))
    )
    (comp (ref "R52")
      (value "10K")
      (footprint "eagle-import:0805")
      (libsource (lib "eagle-import") (part "RESISTOR0805"))
    )
    (comp (ref "R53")
      (value "330")
      (footprint "eagle-import:0805")
      (libsource (lib "eagle-import") (part "RESISTOR0805"))
    )
    (comp (ref "R54")
      (value "10K")
      (footprint "eagle-import:0805")
      (libsource (lib "eagle-import") (part "RESISTOR0805"))
    )
    (comp (ref "R55")
      (value "330")
      (footprint "eagle-import:0805")
      (libsource (lib "eagle-import") (part "RESISTOR0805"))
    )
    (comp (ref "R56")
      (value "330K")
      (footprint "eagle-import:0805")
      (libsource (lib "eagle-import") (part "RESISTOR0805"))
    )
    (comp (ref "R57")
      (value "330K")
      (footprint "eagle-import:0805")
      (libsource (lib "eagle-import") (part "RESISTOR0805"))
    )
    (comp (ref "S1")
      (value "5MS1S102AM2QES")
      (footprint "eagle-import:5MS1S102AM2QES")
      (fields (field (name "RS_PART_NUMBER") "7347292"))
      (libsource (lib "eagle-import") (part "5MS1S102AM2QES"))
    )
    (comp (ref "S2")
      (value "SKRHABE010")
      (footprint "eagle-import:SKRHABE010")
      (fields (field (name "MOUSER_PART_NUMBER") "688-SKRHAB"))
      (libsource (lib "eagle-import") (part "SKRHABE010"))
    )
    (comp (ref "S3")
      (value "AH186061A")
      (footprint "eagle-import:AH186061A")
      (libsource (lib "eagle-import") (part "AH186061A"))
    )
    (comp (ref "S4")
      (value "AH186061A")
      (footprint "eagle-import:AH186061A")
      (libsource (lib "eagle-import") (part "AH186061A"))
    )
    (comp (ref "SJ1")
      (value "SJW")
      (footprint "eagle-import:SJW")
      (libsource (lib "eagle-import") (part "SJW"))
    )
    (comp (ref "SV1")
      (value "MA04-1")
      (footprint "eagle-import:MA04-1")
      (libsource (lib "eagle-import") (part "MA04-1"))
    )
    (comp (ref "SV2")
      (value "MA04-1")
      (footprint "eagle-import:MA04-1")
      (libsource (lib "eagle-import") (part "MA04-1"))
    )
    (comp (ref "SV3")
      (value "MA04-1")
      (footprint "eagle-import:MA04-1")
      (libsource (lib "eagle-import") (part "MA04-1"))
    )
    (comp (ref "SV4")
      (value "MA04-1")
      (footprint "eagle-import:MA04-1")
      (libsource (lib "eagle-import") (part "MA04-1"))
    )
    (comp (ref "U1")
      (value "NC7SB3157P6X")
      (footprint "eagle-import:SOT65P210X110-6N")
      (fields (field (name "MF") "ON Semiconductor"))
      (libsource (lib "eagle-import") (part "NC7SB3157P6X"))
    )
    (comp (ref "U2")
      (value "NC7SB3157P6X")
      (footprint "eagle-import:SOT65P210X110-6N")
      (fields (field (name "MF") "ON Semiconductor"))
      (libsource (lib "eagle-import") (part "NC7SB3157P6X"))
    )
    (comp (ref "U3")
      (value "NC7SB3157P6X")
      (footprint "eagle-import:SOT65P210X110-6N")
      (fields (field (name "MF") "ON Semiconductor"))
      (libsource (lib "eagle-import") (part "NC7SB3157P6X"))
    )
    (comp (ref "U4")
      (value "NC7SB3157P6X")
      (footprint "eagle-import:SOT65P210X110-6N")
      (fields (field (name "MF") "ON Semiconductor"))
      (libsource (lib "eagle-import") (part "NC7SB3157P6X"))
    )
    (comp (ref "U5")
      (value "NC7SB3157P6X")
      (footprint "eagle-import:SOT65P210X110-6N")
      (fields (field (name "MF") "ON Semiconductor"))
      (libsource (lib "eagle-import") (part "NC7SB3157P6X"))
    )
    (comp (ref "U6")
      (value "NC7SB3157P6X")
      (footprint "eagle-import:SOT65P210X110-6N")
      (fields (field (name "MF") "ON Semiconductor"))
      (libsource (lib "eagle-import") (part "NC7SB3157P6X"))
    )
    (comp (ref "U7")
      (value "NC7SB3157P6X")
      (footprint "eagle-import:SOT65P210X110-6N")
      (fields (field (name "MF") "ON Semiconductor"))
      (libsource (lib "eagle-import") (part "NC7SB3157P6X"))
    )
    (comp (ref "U8")
      (value "NC7SB3157P6X")
      (footprint "eagle-import:SOT65P210X110-6N")
      (fields (field (name "MF") "ON Semiconductor"))
      (libsource (lib "eagle-import") (part "NC7SB3157P6X"))
    )
    (comp (ref "U9")
      (value "NC7SB3157P6X")
      (footprint "eagle-import:SOT65P210X110-6N")
      (fields (field (name "MF") "ON Semiconductor"))
      (libsource (lib "eagle-import") (part "NC7SB3157P6X"))
    )
    (comp (ref "U10")
      (value "NC7SB3157P6X")
      (footprint "eagle-import:SOT65P210X110-6N")
      (fields (field (name "MF") "ON Semiconductor"))
      (libsource (lib "eagle-import") (part "NC7SB3157P6X"))
    )
    (comp (ref "U11")
      (value "NC7SB3157P6X")
      (footprint "eagle-import:SOT65P210X110-6N")
      (fields (field (name "MF") "ON Semiconductor"))
      (libsource (lib "eagle-import") (part "NC7SB3157P6X"))
    )
    (comp (ref "U12")
      (value "NC7SB3157P6X")
      (footprint "eagle-import:SOT65P210X110-6N")
      (fields (field (name "MF") "ON Semiconductor"))
      (libsource (lib "eagle-import") (part "NC7SB3157P6X"))
    )
  )
  (nets
    (net (code "1") (name "3V3REG") (class "Default")
      (node (ref "C2") (pin "1") (pinfunction "1_1") (pintype "passive"))
      (node (ref "IC2") (pin "2") (pinfunction "OUT_2") (pintype "passive"))
      (node (ref "IC2") (pin "TAB") (pinfunction "OUT1_TAB") (pintype "passive"))
      (node (ref "JP13") (pin "13") (pinfunction "13_13") (pintype "passive"))
      (node (ref "JP15") (pin "1") (pinfunction "1_1") (pintype "passive"))
      (node (ref "JP5") (pin "7") (pinfunction "7_7") (pintype "passive"))
      (node (ref "JP5") (pin "8") (pinfunction "8_8") (pintype "passive"))
      (node (ref "SV3") (pin "2") (pinfunction "2_2") (pintype "passive"))
    )
    (net (code "2") (name "3V3REG_") (class "Default")
      (node (ref "JP12") (pin "4") (pinfunction "4_4") (pintype "passive"))
      (node (ref "JP14") (pin "1") (pinfunction "1_1") (pintype "passive"))
      (node (ref "JP16") (pin "2") (pinfunction "2_2") (pintype "passive"))
      (node (ref "JP18") (pin "3") (pinfunction "3_3") (pintype "passive"))
      (node (ref "JP20") (pin "2") (pinfunction "2_2") (pintype "passive"))
      (node (ref "JP22") (pin "3") (pinfunction "3_3") (pintype "passive"))
    )
    (net (code "3") (name "5VREG") (class "Default")
      (node (ref "C5") (pin "1") (pinfunction "1_1") (pintype "passive"))
      (node (ref "C6") (pin "1") (pinfunction "1_1") (pintype "passive"))
      (node (ref "IC1") (pin "6") (pinfunction "VCC(B)_6") (pintype "power_in"))
      (node (ref "IC3") (pin "2") (pinfunction "OUT_2") (pintype "passive"))
      (node (ref "IC3") (pin "TAB") (pinfunction "OUT1_TAB") (pintype "passive"))
      (node (ref "IC4") (pin "1") (pinfunction "VDD_1") (pintype "bidirectional"))
      (node (ref "J6") (pin "1") (pinfunction "1_1") (pintype "passive"))
      (node (ref "JP10") (pin "1") (pinfunction "1_1") (pintype "passive"))
      (node (ref "JP13") (pin "12") (pinfunction "12_12") (pintype "passive"))
      (node (ref "JP15") (pin "3") (pinfunction "3_3") (pintype "passive"))
      (node (ref "JP2") (pin "2") (pinfunction "2_2") (pintype "passive"))
      (node (ref "JP5") (pin "10") (pinfunction "10_10") (pintype "passive"))
      (node (ref "JP5") (pin "9") (pinfunction "9_9") (pintype "passive"))
    )
    (net (code "4") (name "5VREG*") (class "Default")
      (node (ref "C9") (pin "1") (pinfunction "1_1") (pintype "passive"))
      (node (ref "IC5") (pin "1") (pinfunction "VDD_1") (pintype "bidirectional"))
      (node (ref "JP6") (pin "1") (pinfunction "1_1") (pintype "passive"))
      (node (ref "Q1") (pin "3") (pinfunction "C_3") (pintype "bidirectional"))
      (node (ref "R9") (pin "2") (pinfunction "2_2") (pintype "passive"))
    )
    (net (code "5") (name "5VREG_") (class "Default")
      (node (ref "IC6") (pin "1") (pinfunction "A0_1") (pintype "bidirectional"))
      (node (ref "IC6") (pin "16") (pinfunction "VDD_16") (pintype "bidirectional"))
      (node (ref "JP12") (pin "5") (pinfunction "5_5") (pintype "passive"))
      (node (ref "JP14") (pin "3") (pinfunction "3_3") (pintype "passive"))
      (node (ref "JP16") (pin "1") (pinfunction "1_1") (pintype "passive"))
      (node (ref "JP18") (pin "1") (pinfunction "1_1") (pintype "passive"))
      (node (ref "JP20") (pin "1") (pinfunction "1_1") (pintype "passive"))
      (node (ref "JP22") (pin "1") (pinfunction "1_1") (pintype "passive"))
      (node (ref "R11") (pin "1") (pinfunction "1_1") (pintype "passive"))
      (node (ref "R14") (pin "1") (pinfunction "1_1") (pintype "passive"))
      (node (ref "R15") (pin "1") (pinfunction "1_1") (pintype "passive"))
      (node (ref "R28") (pin "1") (pinfunction "1_1") (pintype "passive"))
      (node (ref "R29") (pin "1") (pinfunction "1_1") (pintype "passive"))
      (node (ref "S3") (pin "2") (pinfunction "2_2") (pintype "bidirectional"))
      (node (ref "S4") (pin "2") (pinfunction "2_2") (pintype "bidirectional"))
      (node (ref "SV4") (pin "1") (pinfunction "1_1") (pintype "passive"))
    )
    (net (code "6") (name "A0") (class "Default")
      (node (ref "JP8") (pin "1") (pinfunction "1_1") (pintype "passive"))
      (node (ref "U1") (pin "4") (pinfunction "A_4") (pintype "passive"))
    )
    (net (code "7") (name "A0*") (class "Default")
      (node (ref "J3") (pin "1") (pinfunction "1_1") (pintype "passive"))
      (node (ref "JP3") (pin "1") (pinfunction "1_1") (pintype "passive"))
    )
    (net (code "8") (name "A0A") (class "Default")
      (node (ref "Q3") (pin "C") (pinfunction "C1_C") (pintype "passive"))
      (node (ref "R16") (pin "2") (pinfunction "2_2") (pintype "passive"))
      (node (ref "U3") (pin "3") (pinfunction "B0_3") (pintype "passive"))
    )
    (net (code "9") (name "A0B") (class "Default")
      (node (ref "U3") (pin "1") (pinfunction "B1_1") (pintype "passive"))
      (node (ref "U9") (pin "4") (pinfunction "A_4") (pintype "passive"))
    )
    (net (code "10") (name "A0C") (class "Default")
      (node (ref "PTR1") (pin "1") (pinfunction "C_1") (pintype "passive"))
      (node (ref "R36") (pin "2") (pinfunction "2_2") (pintype "passive"))
      (node (ref "U9") (pin "3") (pinfunction "B0_3") (pintype "passive"))
    )
    (net (code "11") (name "A0D") (class "Default")
      (node (ref "Q4") (pin "C") (pinfunction "C1_C") (pintype "passive"))
      (node (ref "R18") (pin "2") (pinfunction "2_2") (pintype "passive"))
      (node (ref "U9") (pin "1") (pinfunction "B1_1") (pintype "passive"))
    )
    (net (code "12") (name "A0S") (class "Default")
      (node (ref "JP12") (pin "16") (pinfunction "16_16") (pintype "passive"))
      (node (ref "U3") (pin "4") (pinfunction "A_4") (pintype "passive"))
    )
    (net (code "13") (name "A0X") (class "Default")
      (node (ref "JP13") (pin "1") (pinfunction "1_1") (pintype "passive"))
      (node (ref "U1") (pin "3") (pinfunction "B0_3") (pintype "passive"))
    )
    (net (code "14") (name "A0Y") (class "Default")
      (node (ref "JP5") (pin "6") (pinfunction "6_6") (pintype "passive"))
      (node (ref "U1") (pin "1") (pinfunction "B1_1") (pintype "passive"))
    )
    (net (code "15") (name "A1") (class "Default")
      (node (ref "JP8") (pin "3") (pinfunction "3_3") (pintype "passive"))
      (node (ref "U2") (pin "4") (pinfunction "A_4") (pintype "passive"))
    )
    (net (code "16") (name "A1*") (class "Default")
      (node (ref "J3") (pin "2") (pinfunction "2_2") (pintype "passive"))
      (node (ref "JP3") (pin "3") (pinfunction "3_3") (pintype "passive"))
    )
    (net (code "17") (name "A1A") (class "Default")
      (node (ref "PTR2") (pin "1") (pinfunction "C_1") (pintype "passive"))
      (node (ref "R38") (pin "2") (pinfunction "2_2") (pintype "passive"))
      (node (ref "U4") (pin "3") (pinfunction "B0_3") (pintype "passive"))
    )
    (net (code "18") (name "A1B") (class "Default")
      (node (ref "PTR3") (pin "1") (pinfunction "C_1") (pintype "passive"))
      (node (ref "R40") (pin "2") (pinfunction "2_2") (pintype "passive"))
      (node (ref "U4") (pin "1") (pinfunction "B1_1") (pintype "passive"))
    )
    (net (code "19") (name "A1S") (class "Default")
      (node (ref "JP12") (pin "15") (pinfunction "15_15") (pintype "passive"))
      (node (ref "U4") (pin "4") (pinfunction "A_4") (pintype "passive"))
    )
    (net (code "20") (name "A1X") (class "Default")
      (node (ref "JP13") (pin "2") (pinfunction "2_2") (pintype "passive"))
      (node (ref "U2") (pin "3") (pinfunction "B0_3") (pintype "passive"))
    )
    (net (code "21") (name "A1Y") (class "Default")
      (node (ref "JP5") (pin "5") (pinfunction "5_5") (pintype "passive"))
      (node (ref "U2") (pin "1") (pinfunction "B1_1") (pintype "passive"))
    )
    (net (code "22") (name "A2") (class "Default")
      (node (ref "JP13") (pin "3") (pinfunction "3_3") (pintype "passive"))
      (node (ref "JP9") (pin "1") (pinfunction "1_1") (pintype "passive"))
    )
    (net (code "23") (name "A2*") (class "Default")
      (node (ref "J3") (pin "3") (pinfunction "3_3") (pintype "passive"))
      (node (ref "JP4") (pin "1") (pinfunction "1_1") (pintype "passive"))
    )
    (net (code "24") (name "A2A") (class "Default")
      (node (ref "Q5") (pin "C") (pinfunction "C1_C") (pintype "passive"))
      (node (ref "R20") (pin "2") (pinfunction "2_2") (pintype "passive"))
      (node (ref "U5") (pin "3") (pinfunction "B0_3") (pintype "passive"))
    )
    (net (code "25") (name "A2B") (class "Default")
      (node (ref "U10") (pin "4") (pinfunction "A_4") (pintype "passive"))
      (node (ref "U5") (pin "1") (pinfunction "B1_1") (pintype "passive"))
    )
    (net (code "26") (name "A2C") (class "Default")
      (node (ref "PTR4") (pin "1") (pinfunction "C_1") (pintype "passive"))
      (node (ref "R42") (pin "2") (pinfunction "2_2") (pintype "passive"))
      (node (ref "U10") (pin "3") (pinfunction "B0_3") (pintype "passive"))
    )
    (net (code "27") (name "A2D") (class "Default")
      (node (ref "PTR5") (pin "1") (pinfunction "C_1") (pintype "passive"))
      (node (ref "R44") (pin "2") (pinfunction "2_2") (pintype "passive"))
      (node (ref "U10") (pin "1") (pinfunction "B1_1") (pintype "passive"))
    )
    (net (code "28") (name "A2S") (class "Default")
      (node (ref "JP12") (pin "14") (pinfunction "14_14") (pintype "passive"))
      (node (ref "U5") (pin "4") (pinfunction "A_4") (pintype "passive"))
    )
    (net (code "29") (name "A3") (class "Default")
      (node (ref "JP13") (pin "14") (pinfunction "14_14") (pintype "passive"))
      (node (ref "JP9") (pin "2") (pinfunction "2_2") (pintype "passive"))
    )
    (net (code "30") (name "A3*") (class "Default")
      (node (ref "J3") (pin "4") (pinfunction "4_4") (pintype "passive"))
      (node (ref "JP4") (pin "2") (pinfunction "2_2") (pintype "passive"))
    )
    (net (code "31") (name "A3A") (class "Default")
      (node (ref "PTR6") (pin "1") (pinfunction "C_1") (pintype "passive"))
      (node (ref "R46") (pin "2") (pinfunction "2_2") (pintype "passive"))
      (node (ref "U6") (pin "3") (pinfunction "B0_3") (pintype "passive"))
    )
    (net (code "32") (name "A3B") (class "Default")
      (node (ref "U11") (pin "4") (pinfunction "A_4") (pintype "passive"))
      (node (ref "U6") (pin "1") (pinfunction "B1_1") (pintype "passive"))
    )
    (net (code "33") (name "A3C") (class "Default")
      (node (ref "PTR7") (pin "1") (pinfunction "C_1") (pintype "passive"))
      (node (ref "R48") (pin "2") (pinfunction "2_2") (pintype "passive"))
      (node (ref "U11") (pin "3") (pinfunction "B0_3") (pintype "passive"))
    )
    (net (code "34") (name "A3D") (class "Default")
      (node (ref "Q6") (pin "C") (pinfunction "C1_C") (pintype "passive"))
      (node (ref "R22") (pin "2") (pinfunction "2_2") (pintype "passive"))
      (node (ref "U11") (pin "1") (pinfunction "B1_1") (pintype "passive"))
    )
    (net (code "35") (name "A3S") (class "Default")
      (node (ref "JP12") (pin "3") (pinfunction "3_3") (pintype "passive"))
      (node (ref "U6") (pin "4") (pinfunction "A_4") (pintype "passive"))
    )
    (net (code "36") (name "A4") (class "Default")
      (node (ref "JP13") (pin "15") (pinfunction "15_15") (pintype "passive"))
      (node (ref "JP9") (pin "3") (pinfunction "3_3") (pintype "passive"))
    )
    (net (code "37") (name "A4*") (class "Default")
      (node (ref "J3") (pin "5") (pinfunction "5_5") (pintype "passive"))
      (node (ref "JP4") (pin "3") (pinfunction "3_3") (pintype "passive"))
    )
    (net (code "38") (name "A4A") (class "Default")
      (node (ref "PTR8") (pin "1") (pinfunction "C_1") (pintype "passive"))
      (node (ref "R50") (pin "2") (pinfunction "2_2") (pintype "passive"))
      (node (ref "U7") (pin "3") (pinfunction "B0_3") (pintype "passive"))
    )
    (net (code "39") (name "A4B") (class "Default")
      (node (ref "PTR9") (pin "1") (pinfunction "C_1") (pintype "passive"))
      (node (ref "R52") (pin "2") (pinfunction "2_2") (pintype "passive"))
      (node (ref "U7") (pin "1") (pinfunction "B1_1") (pintype "passive"))
    )
    (net (code "40") (name "A4S") (class "Default")
      (node (ref "JP12") (pin "2") (pinfunction "2_2") (pintype "passive"))
      (node (ref "U7") (pin "4") (pinfunction "A_4") (pintype "passive"))
    )
    (net (code "41") (name "A5") (class "Default")
      (node (ref "JP13") (pin "16") (pinfunction "16_16") (pintype "passive"))
      (node (ref "JP9") (pin "4") (pinfunction "4_4") (pintype "passive"))
    )
    (net (code "42") (name "A5*") (class "Default")
      (node (ref "J3") (pin "6") (pinfunction "6_6") (pintype "passive"))
      (node (ref "JP4") (pin "4") (pinfunction "4_4") (pintype "passive"))
    )
    (net (code "43") (name "A5A") (class "Default")
      (node (ref "Q7") (pin "C") (pinfunction "C1_C") (pintype "passive"))
      (node (ref "R24") (pin "2") (pinfunction "2_2") (pintype "passive"))
      (node (ref "U8") (pin "3") (pinfunction "B0_3") (pintype "passive"))
    )
    (net (code "44") (name "A5B") (class "Default")
      (node (ref "U12") (pin "4") (pinfunction "A_4") (pintype "passive"))
      (node (ref "U8") (pin "1") (pinfunction "B1_1") (pintype "passive"))
    )
    (net (code "45") (name "A5C") (class "Default")
      (node (ref "PTR10") (pin "1") (pinfunction "C_1") (pintype "passive"))
      (node (ref "R54") (pin "2") (pinfunction "2_2") (pintype "passive"))
      (node (ref "U12") (pin "3") (pinfunction "B0_3") (pintype "passive"))
    )
    (net (code "46") (name "A5D") (class "Default")
      (node (ref "Q8") (pin "C") (pinfunction "C1_C") (pintype "passive"))
      (node (ref "R26") (pin "2") (pinfunction "2_2") (pintype "passive"))
      (node (ref "U12") (pin "1") (pinfunction "B1_1") (pintype "passive"))
    )
    (net (code "47") (name "A5S") (class "Default")
      (node (ref "JP12") (pin "1") (pinfunction "1_1") (pintype "passive"))
      (node (ref "U8") (pin "4") (pinfunction "A_4") (pintype "passive"))
    )
    (net (code "48") (name "D0") (class "Default")
      (node (ref "DRV2") (pin "M0") (pinfunction "M0_M0") (pintype "bidirectional"))
      (node (ref "JP11") (pin "2") (pinfunction "2_2") (pintype "passive"))
    )
    (net (code "49") (name "D0*") (class "Default")
      (node (ref "J5") (pin "1") (pinfunction "1_1") (pintype "passive"))
      (node (ref "JP7") (pin "2") (pinfunction "2_2") (pintype "passive"))
    )
    (net (code "50") (name "D1") (class "Default")
      (node (ref "DRV2") (pin "M1") (pinfunction "M1_M1") (pintype "bidirectional"))
      (node (ref "JP11") (pin "4") (pinfunction "4_4") (pintype "passive"))
    )
    (net (code "51") (name "D1*") (class "Default")
      (node (ref "J5") (pin "2") (pinfunction "2_2") (pintype "passive"))
      (node (ref "JP7") (pin "4") (pinfunction "4_4") (pintype "passive"))
    )
    (net (code "52") (name "D2") (class "Default")
      (node (ref "DRV1") (pin "M0") (pinfunction "M0_M0") (pintype "bidirectional"))
      (node (ref "JP11") (pin "8") (pinfunction "8_8") (pintype "passive"))
    )
    (net (code "53") (name "D2*") (class "Default")
      (node (ref "J5") (pin "3") (pinfunction "3_3") (pintype "passive"))
      (node (ref "JP7") (pin "8") (pinfunction "8_8") (pintype "passive"))
    )
    (net (code "54") (name "D3") (class "Default")
      (node (ref "JP11") (pin "6") (pinfunction "6_6") (pintype "passive"))
      (node (ref "JP5") (pin "4") (pinfunction "4_4") (pintype "passive"))
    )
    (net (code "55") (name "D3*") (class "Default")
      (node (ref "J5") (pin "4") (pinfunction "4_4") (pintype "passive"))
      (node (ref "JP7") (pin "6") (pinfunction "6_6") (pintype "passive"))
    )
    (net (code "56") (name "D4") (class "Default")
      (node (ref "DRV1") (pin "M1") (pinfunction "M1_M1") (pintype "bidirectional"))
      (node (ref "JP11") (pin "7") (pinfunction "7_7") (pintype "passive"))
    )
    (net (code "57") (name "D4*") (class "Default")
      (node (ref "J5") (pin "5") (pinfunction "5_5") (pintype "passive"))
      (node (ref "JP7") (pin "7") (pinfunction "7_7") (pintype "passive"))
    )
    (net (code "58") (name "D5") (class "Default")
      (node (ref "JP11") (pin "5") (pinfunction "5_5") (pintype "passive"))
      (node (ref "JP5") (pin "3") (pinfunction "3_3") (pintype "passive"))
    )
    (net (code "59") (name "D5*") (class "Default")
      (node (ref "J5") (pin "6") (pinfunction "6_6") (pintype "passive"))
      (node (ref "JP7") (pin "5") (pinfunction "5_5") (pintype "passive"))
    )
    (net (code "60") (name "D6") (class "Default")
      (node (ref "IC1") (pin "3") (pinfunction "A_3") (pintype "bidirectional"))
      (node (ref "JP1") (pin "1") (pinfunction "1_1") (pintype "passive"))
      (node (ref "JP11") (pin "3") (pinfunction "3_3") (pintype "passive"))
    )
    (net (code "61") (name "D6*") (class "Default")
      (node (ref "J5") (pin "7") (pinfunction "7_7") (pintype "passive"))
      (node (ref "JP7") (pin "3") (pinfunction "3_3") (pintype "passive"))
    )
    (net (code "62") (name "D7*") (class "Default")
      (node (ref "J5") (pin "8") (pinfunction "8_8") (pintype "passive"))
      (node (ref "R8") (pin "2") (pinfunction "2_2") (pintype "passive"))
    )
    (net (code "63") (name "D8") (class "Default")
      (node (ref "JP10") (pin "4") (pinfunction "4_4") (pintype "passive"))
      (node (ref "JP13") (pin "10") (pinfunction "10_10") (pintype "passive"))
    )
    (net (code "64") (name "D8*") (class "Default")
      (node (ref "J4") (pin "1") (pinfunction "1_1") (pintype "passive"))
      (node (ref "JP6") (pin "4") (pinfunction "4_4") (pintype "passive"))
    )
    (net (code "65") (name "D8_") (class "Default")
      (node (ref "JP12") (pin "7") (pinfunction "7_7") (pintype "passive"))
      (node (ref "R56") (pin "2") (pinfunction "2_2") (pintype "passive"))
      (node (ref "U3") (pin "6") (pinfunction "S_6") (pintype "input"))
      (node (ref "U4") (pin "6") (pinfunction "S_6") (pintype "input"))
      (node (ref "U5") (pin "6") (pinfunction "S_6") (pintype "input"))
      (node (ref "U6") (pin "6") (pinfunction "S_6") (pintype "input"))
      (node (ref "U7") (pin "6") (pinfunction "S_6") (pintype "input"))
      (node (ref "U8") (pin "6") (pinfunction "S_6") (pintype "input"))
    )
    (net (code "66") (name "D9") (class "Default")
      (node (ref "JP10") (pin "6") (pinfunction "6_6") (pintype "passive"))
      (node (ref "JP13") (pin "7") (pinfunction "7_7") (pintype "passive"))
    )
    (net (code "67") (name "D9*") (class "Default")
      (node (ref "J4") (pin "2") (pinfunction "2_2") (pintype "passive"))
      (node (ref "JP6") (pin "6") (pinfunction "6_6") (pintype "passive"))
    )
    (net (code "68") (name "D9_") (class "Default")
      (node (ref "JP12") (pin "10") (pinfunction "10_10") (pintype "passive"))
      (node (ref "R57") (pin "2") (pinfunction "2_2") (pintype "passive"))
      (node (ref "U10") (pin "6") (pinfunction "S_6") (pintype "input"))
      (node (ref "U11") (pin "6") (pinfunction "S_6") (pintype "input"))
      (node (ref "U12") (pin "6") (pinfunction "S_6") (pintype "input"))
      (node (ref "U9") (pin "6") (pinfunction "S_6") (pintype "input"))
    )
    (net (code "69") (name "D10") (class "Default")
      (node (ref "DRV2") (pin "DIR") (pinfunction "DIR_DIR") (pintype "bidirectional"))
      (node (ref "JP10") (pin "8") (pinfunction "8_8") (pintype "passive"))
    )
    (net (code "70") (name "D10*") (class "Default")
      (node (ref "J4") (pin "3") (pinfunction "3_3") (pintype "passive"))
      (node (ref "JP6") (pin "8") (pinfunction "8_8") (pintype "passive"))
    )
    (net (code "71") (name "D11") (class "Default")
      (node (ref "DRV2") (pin "STEP") (pinfunction "STEP_STEP") (pintype "bidirectional"))
      (node (ref "JP10") (pin "10") (pinfunction "10_10") (pintype "passive"))
    )
    (net (code "72") (name "D11*") (class "Default")
      (node (ref "J4") (pin "4") (pinfunction "4_4") (pintype "passive"))
      (node (ref "JP6") (pin "10") (pinfunction "10_10") (pintype "passive"))
    )
    (net (code "73") (name "D12") (class "Default")
      (node (ref "DRV1") (pin "DIR") (pinfunction "DIR_DIR") (pintype "bidirectional"))
      (node (ref "JP10") (pin "9") (pinfunction "9_9") (pintype "passive"))
    )
    (net (code "74") (name "D12*") (class "Default")
      (node (ref "J4") (pin "5") (pinfunction "5_5") (pintype "passive"))
      (node (ref "JP6") (pin "9") (pinfunction "9_9") (pintype "passive"))
    )
    (net (code "75") (name "D13") (class "Default")
      (node (ref "DRV1") (pin "STEP") (pinfunction "STEP_STEP") (pintype "bidirectional"))
      (node (ref "JP10") (pin "7") (pinfunction "7_7") (pintype "passive"))
    )
    (net (code "76") (name "D13*") (class "Default")
      (node (ref "J4") (pin "6") (pinfunction "6_6") (pintype "passive"))
      (node (ref "JP6") (pin "7") (pinfunction "7_7") (pintype "passive"))
    )
    (net (code "77") (name "DOWNEN_") (class "Default")
      (node (ref "IC6") (pin "6") (pinfunction "P2_6") (pintype "bidirectional"))
      (node (ref "R34") (pin "2") (pinfunction "2_2") (pintype "passive"))
    )
    (net (code "78") (name "FOWEN_") (class "Default")
      (node (ref "IC6") (pin "7") (pinfunction "P3_7") (pintype "bidirectional"))
      (node (ref "R13") (pin "2") (pinfunction "2_2") (pintype "passive"))
    )
    (net (code "79") (name "GND") (class "Default")
      (node (ref "C1") (pin "2") (pinfunction "2_2") (pintype "passive"))
      (node (ref "C10") (pin "2") (pinfunction "2_2") (pintype "passive"))
      (node (ref "C11") (pin "2") (pinfunction "2_2") (pintype "passive"))
      (node (ref "C12") (pin "2") (pinfunction "2_2") (pintype "passive"))
      (node (ref "C13") (pin "2") (pinfunction "2_2") (pintype "passive"))
      (node (ref "C14") (pin "2") (pinfunction "2_2") (pintype "passive"))
      (node (ref "C15") (pin "2") (pinfunction "2_2") (pintype "passive"))
      (node (ref "C16") (pin "2") (pinfunction "2_2") (pintype "passive"))
      (node (ref "C17") (pin "2") (pinfunction "2_2") (pintype "passive"))
      (node (ref "C18") (pin "1") (pinfunction "1_1") (pintype "passive"))
      (node (ref "C19") (pin "1") (pinfunction "1_1") (pintype "passive"))
      (node (ref "C2") (pin "2") (pinfunction "2_2") (pintype "passive"))
      (node (ref "C20") (pin "1") (pinfunction "1_1") (pintype "passive"))
      (node (ref "C21") (pin "1") (pinfunction "1_1") (pintype "passive"))
      (node (ref "C22") (pin "1") (pinfunction "1_1") (pintype "passive"))
      (node (ref "C23") (pin "1") (pinfunction "1_1") (pintype "passive"))
      (node (ref "C24") (pin "1") (pinfunction "1_1") (pintype "passive"))
      (node (ref "C25") (pin "1") (pinfunction "1_1") (pintype "passive"))
      (node (ref "C26") (pin "1") (pinfunction "1_1") (pintype "passive"))
      (node (ref "C27") (pin "1") (pinfunction "1_1") (pintype "passive"))
      (node (ref "C28") (pin "1") (pinfunction "1_1") (pintype "passive"))
      (node (ref "C29") (pin "1") (pinfunction "1_1") (pintype "passive"))
      (node (ref "C3") (pin "1") (pinfunction "1_1") (pintype "bidirectional"))
      (node (ref "C30") (pin "1") (pinfunction "1_1") (pintype "passive"))
      (node (ref "C31") (pin "1") (pinfunction "1_1") (pintype "passive"))
      (node (ref "C32") (pin "1") (pinfunction "1_1") (pintype "passive"))
      (node (ref "C33") (pin "1") (pinfunction "1_1") (pintype "passive"))
      (node (ref "C4") (pin "2") (pinfunction "2_2") (pintype "passive"))
      (node (ref "C5") (pin "2") (pinfunction "2_2") (pintype "passive"))
      (node (ref "C6") (pin "2") (pinfunction "2_2") (pintype "passive"))
      (node (ref "C7") (pin "2") (pinfunction "2_2") (pintype "passive"))
      (node (ref "C8") (pin "1") (pinfunction "1_1") (pintype "bidirectional"))
      (node (ref "C9") (pin "2") (pinfunction "2_2") (pintype "passive"))
      (node (ref "D1") (pin "C") (pinfunction "C_C") (pintype "passive"))
      (node (ref "D12") (pin "C") (pinfunction "C_C") (pintype "passive"))
      (node (ref "D13") (pin "C") (pinfunction "C_C") (pintype "passive"))
      (node (ref "D14") (pin "C") (pinfunction "C_C") (pintype "passive"))
      (node (ref "D15") (pin "C") (pinfunction "C_C") (pintype "passive"))
      (node (ref "D16") (pin "C") (pinfunction "C_C") (pintype "passive"))
      (node (ref "D17") (pin "C") (pinfunction "C_C") (pintype "passive"))
      (node (ref "D3") (pin "C") (pinfunction "C_C") (pintype "passive"))
      (node (ref "DRV1") (pin "GND0") (pinfunction "GND0_GND0") (pintype "bidirectional"))
      (node (ref "DRV1") (pin "GND1") (pinfunction "GND1_GND1") (pintype "bidirectional"))
      (node (ref "DRV2") (pin "GND0") (pinfunction "GND0_GND0") (pintype "bidirectional"))
      (node (ref "DRV2") (pin "GND1") (pinfunction "GND1_GND1") (pintype "bidirectional"))
      (node (ref "IC1") (pin "2") (pinfunction "GND_2") (pintype "power_in"))
      (node (ref "IC2") (pin "1") (pinfunction "GND_1") (pintype "input"))
      (node (ref "IC3") (pin "1") (pinfunction "GND_1") (pintype "input"))
      (node (ref "IC4") (pin "2") (pinfunction "VSS_2") (pintype "bidirectional"))
      (node (ref "IC5") (pin "2") (pinfunction "VSS_2") (pintype "bidirectional"))
      (node (ref "IC6") (pin "2") (pinfunction "A1_2") (pintype "bidirectional"))
      (node (ref "IC6") (pin "3") (pinfunction "A2_3") (pintype "bidirectional"))
      (node (ref "IC6") (pin "8") (pinfunction "VSS_8") (pintype "bidirectional"))
      (node (ref "IC7") (pin "1") (pinfunction "A0_1") (pintype "bidirectional"))
      (node (ref "IC7") (pin "2") (pinfunction "A1_2") (pintype "bidirectional"))
      (node (ref "IC7") (pin "3") (pinfunction "A2_3") (pintype "bidirectional"))
      (node (ref "IC7") (pin "8") (pinfunction "VSS_8") (pintype "bidirectional"))
      (node (ref "IRLED1") (pin "2") (pinfunction "C_2") (pintype "passive"))
      (node (ref "IRLED10") (pin "2") (pinfunction "C_2") (pintype "passive"))
      (node (ref "IRLED11") (pin "2") (pinfunction "C_2") (pintype "passive"))
      (node (ref "IRLED2") (pin "2") (pinfunction "C_2") (pintype "passive"))
      (node (ref "IRLED3") (pin "2") (pinfunction "C_2") (pintype "passive"))
      (node (ref "IRLED4") (pin "2") (pinfunction "C_2") (pintype "passive"))
      (node (ref "IRLED5") (pin "2") (pinfunction "C_2") (pintype "passive"))
      (node (ref "IRLED6") (pin "2") (pinfunction "C_2") (pintype "passive"))
      (node (ref "IRLED7") (pin "2") (pinfunction "C_2") (pintype "passive"))
      (node (ref "IRLED8") (pin "2") (pinfunction "C_2") (pintype "passive"))
      (node (ref "IRLED9") (pin "2") (pinfunction "C_2") (pintype "passive"))
      (node (ref "J1") (pin "1") (pinfunction "1_1") (pintype "passive"))
      (node (ref "J2") (pin "6") (pinfunction "6_6") (pintype "passive"))
      (node (ref "J2") (pin "7") (pinfunction "7_7") (pintype "passive"))
      (node (ref "J4") (pin "7") (pinfunction "7_7") (pintype "passive"))
      (node (ref "J6") (pin "2") (pinfunction "2_2") (pintype "passive"))
      (node (ref "JP10") (pin "2") (pinfunction "2_2") (pintype "passive"))
      (node (ref "JP11") (pin "1") (pinfunction "1_1") (pintype "passive"))
      (node (ref "JP12") (pin "11") (pinfunction "11_11") (pintype "passive"))
      (node (ref "JP12") (pin "6") (pinfunction "6_6") (pintype "passive"))
      (node (ref "JP13") (pin "11") (pinfunction "11_11") (pintype "passive"))
      (node (ref "JP13") (pin "6") (pinfunction "6_6") (pintype "passive"))
      (node (ref "JP3") (pin "2") (pinfunction "2_2") (pintype "passive"))
      (node (ref "JP5") (pin "13") (pinfunction "13_13") (pintype "passive"))
      (node (ref "JP5") (pin "14") (pinfunction "14_14") (pintype "passive"))
      (node (ref "JP6") (pin "2") (pinfunction "2_2") (pintype "passive"))
      (node (ref "JP7") (pin "1") (pinfunction "1_1") (pintype "passive"))
      (node (ref "JP8") (pin "2") (pinfunction "2_2") (pintype "passive"))
      (node (ref "LS1") (pin "+") (pinfunction "1_+") (pintype "passive"))
      (node (ref "PLED1") (pin "2") (pinfunction "VSS_2") (pintype "bidirectional"))
      (node (ref "PLED2") (pin "2") (pinfunction "VSS_2") (pintype "bidirectional"))
      (node (ref "PLED3") (pin "2") (pinfunction "VSS_2") (pintype "bidirectional"))
      (node (ref "PLED4") (pin "2") (pinfunction "VSS_2") (pintype "bidirectional"))
      (node (ref "PLED5") (pin "2") (pinfunction "VSS_2") (pintype "bidirectional"))
      (node (ref "PLED6") (pin "2") (pinfunction "VSS_2") (pintype "bidirectional"))
      (node (ref "PLED7") (pin "2") (pinfunction "VSS_2") (pintype "bidirectional"))
      (node (ref "PLED8") (pin "2") (pinfunction "VSS_2") (pintype "bidirectional"))
      (node (ref "PLED9") (pin "2") (pinfunction "VSS_2") (pintype "bidirectional"))
      (node (ref "PTR1") (pin "2") (pinfunction "E_2") (pintype "passive"))
      (node (ref "PTR10") (pin "2") (pinfunction "E_2") (pintype "passive"))
      (node (ref "PTR2") (pin "2") (pinfunction "E_2") (pintype "passive"))
      (node (ref "PTR3") (pin "2") (pinfunction "E_2") (pintype "passive"))
      (node (ref "PTR4") (pin "2") (pinfunction "E_2") (pintype "passive"))
      (node (ref "PTR5") (pin "2") (pinfunction "E_2") (pintype "passive"))
      (node (ref "PTR6") (pin "2") (pinfunction "E_2") (pintype "passive"))
      (node (ref "PTR7") (pin "2") (pinfunction "E_2") (pintype "passive"))
      (node (ref "PTR8") (pin "2") (pinfunction "E_2") (pintype "passive"))
      (node (ref "PTR9") (pin "2") (pinfunction "E_2") (pintype "passive"))
      (node (ref "Q3") (pin "E") (pinfunction "E1_E") (pintype "passive"))
      (node (ref "Q4") (pin "E") (pinfunction "E1_E") (pintype "passive"))
      (node (ref "Q5") (pin "E") (pinfunction "E1_E") (pintype "passive"))
      (node (ref "Q6") (pin "E") (pinfunction "E1_E") (pintype "passive"))
      (node (ref "Q7") (pin "E") (pinfunction "E1_E") (pintype "passive"))
      (node (ref "Q8") (pin "E") (pinfunction "E1_E") (pintype "passive"))
      (node (ref "R10") (pin "2") (pinfunction "2_2") (pintype "passive"))
      (node (ref "R12") (pin "1") (pinfunction "1_1") (pintype "passive"))
      (node (ref "R2") (pin "2") (pinfunction "2_2") (pintype "passive"))
      (node (ref "R3") (pin "1") (pinfunction "1_1") (pintype "passive"))
      (node (ref "R4") (pin "1") (pinfunction "1_1") (pintype "passive"))
      (node (ref "R5") (pin "1") (pinfunction "1_1") (pintype "passive"))
      (node (ref "R56") (pin "1") (pinfunction "1_1") (pintype "passive"))
      (node (ref "R57") (pin "1") (pinfunction "1_1") (pintype "passive"))
      (node (ref "R6") (pin "1") (pinfunction "1_1") (pintype "passive"))
      (node (ref "S3") (pin "3") (pinfunction "3_3") (pintype "bidirectional"))
      (node (ref "S4") (pin "3") (pinfunction "3_3") (pintype "bidirectional"))
      (node (ref "SV3") (pin "1") (pinfunction "1_1") (pintype "passive"))
      (node (ref "SV4") (pin "2") (pinfunction "2_2") (pintype "passive"))
      (node (ref "U1") (pin "2") (pinfunction "GND_2") (pintype "passive"))
      (node (ref "U10") (pin "2") (pinfunction "GND_2") (pintype "passive"))
      (node (ref "U11") (pin "2") (pinfunction "GND_2") (pintype "passive"))
      (node (ref "U12") (pin "2") (pinfunction "GND_2") (pintype "passive"))
      (node (ref "U2") (pin "2") (pinfunction "GND_2") (pintype "passive"))
      (node (ref "U3") (pin "2") (pinfunction "GND_2") (pintype "passive"))
      (node (ref "U4") (pin "2") (pinfunction "GND_2") (pintype "passive"))
      (node (ref "U5") (pin "2") (pinfunction "GND_2") (pintype "passive"))
      (node (ref "U6") (pin "2") (pinfunction "GND_2") (pintype "passive"))
      (node (ref "U7") (pin "2") (pinfunction "GND_2") (pintype "passive"))
      (node (ref "U8") (pin "2") (pinfunction "GND_2") (pintype "passive"))
      (node (ref "U9") (pin "2") (pinfunction "GND_2") (pintype "passive"))
    )
    (net (code "80") (name "MOTL_EN") (class "Default")
      (node (ref "DRV2") (pin "EN") (pinfunction "EN_EN") (pintype "bidirectional"))
      (node (ref "IC7") (pin "4") (pinfunction "P0_4") (pintype "bidirectional"))
    )
    (net (code "81") (name "MOTR_EN") (class "Default")
      (node (ref "DRV1") (pin "EN") (pinfunction "EN_EN") (pintype "bidirectional"))
      (node (ref "IC7") (pin "5") (pinfunction "P1_5") (pintype "bidirectional"))
    )
    (net (code "82") (name "MUL0") (class "Default")
      (node (ref "IC7") (pin "6") (pinfunction "P2_6") (pintype "bidirectional"))
      (node (ref "R12") (pin "2") (pinfunction "2_2") (pintype "passive"))
      (node (ref "U1") (pin "6") (pinfunction "S_6") (pintype "input"))
      (node (ref "U2") (pin "6") (pinfunction "S_6") (pintype "input"))
    )
    (net (code "83") (name "Net-(C18-Pad2)") (class "Default")
      (node (ref "C18") (pin "2") (pinfunction "2_2") (pintype "passive"))
      (node (ref "C19") (pin "2") (pinfunction "2_2") (pintype "passive"))
      (node (ref "C20") (pin "2") (pinfunction "2_2") (pintype "passive"))
      (node (ref "C21") (pin "2") (pinfunction "2_2") (pintype "passive"))
      (node (ref "C22") (pin "2") (pinfunction "2_2") (pintype "passive"))
      (node (ref "C23") (pin "2") (pinfunction "2_2") (pintype "passive"))
      (node (ref "JP19") (pin "2") (pinfunction "2_2") (pintype "passive"))
      (node (ref "R16") (pin "1") (pinfunction "1_1") (pintype "passive"))
      (node (ref "R18") (pin "1") (pinfunction "1_1") (pintype "passive"))
      (node (ref "R20") (pin "1") (pinfunction "1_1") (pintype "passive"))
      (node (ref "R22") (pin "1") (pinfunction "1_1") (pintype "passive"))
      (node (ref "R24") (pin "1") (pinfunction "1_1") (pintype "passive"))
      (node (ref "R26") (pin "1") (pinfunction "1_1") (pintype "passive"))
    )
    (net (code "84") (name "Net-(C24-Pad2)") (class "Default")
      (node (ref "C24") (pin "2") (pinfunction "2_2") (pintype "passive"))
      (node (ref "C25") (pin "2") (pinfunction "2_2") (pintype "passive"))
      (node (ref "C26") (pin "2") (pinfunction "2_2") (pintype "passive"))
      (node (ref "C27") (pin "2") (pinfunction "2_2") (pintype "passive"))
      (node (ref "C28") (pin "2") (pinfunction "2_2") (pintype "passive"))
      (node (ref "C29") (pin "2") (pinfunction "2_2") (pintype "passive"))
      (node (ref "C30") (pin "2") (pinfunction "2_2") (pintype "passive"))
      (node (ref "C31") (pin "2") (pinfunction "2_2") (pintype "passive"))
      (node (ref "C32") (pin "2") (pinfunction "2_2") (pintype "passive"))
      (node (ref "C33") (pin "2") (pinfunction "2_2") (pintype "passive"))
      (node (ref "JP23") (pin "2") (pinfunction "2_2") (pintype "passive"))
      (node (ref "R36") (pin "1") (pinfunction "1_1") (pintype "passive"))
      (node (ref "R38") (pin "1") (pinfunction "1_1") (pintype "passive"))
      (node (ref "R40") (pin "1") (pinfunction "1_1") (pintype "passive"))
      (node (ref "R42") (pin "1") (pinfunction "1_1") (pintype "passive"))
      (node (ref "R44") (pin "1") (pinfunction "1_1") (pintype "passive"))
      (node (ref "R46") (pin "1") (pinfunction "1_1") (pintype "passive"))
      (node (ref "R48") (pin "1") (pinfunction "1_1") (pintype "passive"))
      (node (ref "R50") (pin "1") (pinfunction "1_1") (pintype "passive"))
      (node (ref "R52") (pin "1") (pinfunction "1_1") (pintype "passive"))
      (node (ref "R54") (pin "1") (pinfunction "1_1") (pintype "passive"))
    )
    (net (code "85") (name "Net-(D1-PadA)") (class "Default")
      (node (ref "D1") (pin "A") (pinfunction "A_A") (pintype "passive"))
      (node (ref "R7") (pin "2") (pinfunction "2_2") (pintype "passive"))
    )
    (net (code "86") (name "Net-(D2-PadC)") (class "Default")
      (node (ref "D2") (pin "C") (pinfunction "C_C") (pintype "passive"))
      (node (ref "JP8") (pin "4") (pinfunction "4_4") (pintype "passive"))
    )
    (net (code "87") (name "Net-(D3-PadA)") (class "Default")
      (node (ref "D3") (pin "A") (pinfunction "A_A") (pintype "passive"))
      (node (ref "R11") (pin "2") (pinfunction "2_2") (pintype "passive"))
    )
    (net (code "88") (name "Net-(D4-PadA)") (class "Default")
      (node (ref "D4") (pin "A") (pinfunction "A_A") (pintype "passive"))
      (node (ref "R14") (pin "2") (pinfunction "2_2") (pintype "passive"))
    )
    (net (code "89") (name "Net-(D5-PadA)") (class "Default")
      (node (ref "D5") (pin "A") (pinfunction "A_A") (pintype "passive"))
      (node (ref "R15") (pin "2") (pinfunction "2_2") (pintype "passive"))
    )
    (net (code "90") (name "Net-(D6-PadA)") (class "Default")
      (node (ref "D6") (pin "A") (pinfunction "A_A") (pintype "passive"))
      (node (ref "R28") (pin "2") (pinfunction "2_2") (pintype "passive"))
    )
    (net (code "91") (name "Net-(D7-PadA)") (class "Default")
      (node (ref "D7") (pin "A") (pinfunction "A_A") (pintype "passive"))
      (node (ref "R29") (pin "2") (pinfunction "2_2") (pintype "passive"))
    )
    (net (code "92") (name "Net-(D8-PadA)") (class "Default")
      (node (ref "D8") (pin "A") (pinfunction "A_A") (pintype "passive"))
      (node (ref "R30") (pin "2") (pinfunction "2_2") (pintype "passive"))
    )
    (net (code "93") (name "Net-(D9-PadA)") (class "Default")
      (node (ref "D9") (pin "A") (pinfunction "A_A") (pintype "passive"))
      (node (ref "R31") (pin "2") (pinfunction "2_2") (pintype "passive"))
    )
    (net (code "94") (name "Net-(D10-PadA)") (class "Default")
      (node (ref "D10") (pin "A") (pinfunction "A_A") (pintype "passive"))
      (node (ref "R32") (pin "2") (pinfunction "2_2") (pintype "passive"))
    )
    (net (code "95") (name "Net-(D11-PadA)") (class "Default")
      (node (ref "D11") (pin "A") (pinfunction "A_A") (pintype "passive"))
      (node (ref "R33") (pin "2") (pinfunction "2_2") (pintype "passive"))
    )
    (net (code "96") (name "Net-(D12-PadA)") (class "Default")
      (node (ref "D12") (pin "A") (pinfunction "A_A") (pintype "passive"))
      (node (ref "R17") (pin "2") (pinfunction "2_2") (pintype "passive"))
    )
    (net (code "97") (name "Net-(D13-PadA)") (class "Default")
      (node (ref "D13") (pin "A") (pinfunction "A_A") (pintype "passive"))
      (node (ref "R19") (pin "2") (pinfunction "2_2") (pintype "passive"))
    )
    (net (code "98") (name "Net-(D14-PadA)") (class "Default")
      (node (ref "D14") (pin "A") (pinfunction "A_A") (pintype "passive"))
      (node (ref "R21") (pin "2") (pinfunction "2_2") (pintype "passive"))
    )
    (net (code "99") (name "Net-(D15-PadA)") (class "Default")
      (node (ref "D15") (pin "A") (pinfunction "A_A") (pintype "passive"))
      (node (ref "R23") (pin "2") (pinfunction "2_2") (pintype "passive"))
    )
    (net (code "100") (name "Net-(D16-PadA)") (class "Default")
      (node (ref "D16") (pin "A") (pinfunction "A_A") (pintype "passive"))
      (node (ref "R25") (pin "2") (pinfunction "2_2") (pintype "passive"))
    )
    (net (code "101") (name "Net-(D17-PadA)") (class "Default")
      (node (ref "D17") (pin "A") (pinfunction "A_A") (pintype "passive"))
      (node (ref "R27") (pin "2") (pinfunction "2_2") (pintype "passive"))
    )
    (net (code "102") (name "Net-(DRV1-PadA1)") (class "Default")
      (node (ref "DRV1") (pin "A1") (pinfunction "A1_A1") (pintype "bidirectional"))
      (node (ref "SV1") (pin "3") (pinfunction "3_3") (pintype "passive"))
    )
    (net (code "103") (name "Net-(DRV1-PadA2)") (class "Default")
      (node (ref "DRV1") (pin "A2") (pinfunction "A2_A2") (pintype "bidirectional"))
      (node (ref "SV1") (pin "4") (pinfunction "4_4") (pintype "passive"))
    )
    (net (code "104") (name "Net-(DRV1-PadB1)") (class "Default")
      (node (ref "DRV1") (pin "B1") (pinfunction "B1_B1") (pintype "bidirectional"))
      (node (ref "SV1") (pin "2") (pinfunction "2_2") (pintype "passive"))
    )
    (net (code "105") (name "Net-(DRV1-PadB2)") (class "Default")
      (node (ref "DRV1") (pin "B2") (pinfunction "B2_B2") (pintype "bidirectional"))
      (node (ref "SV1") (pin "1") (pinfunction "1_1") (pintype "passive"))
    )
    (net (code "106") (name "Net-(DRV2-PadA1)") (class "Default")
      (node (ref "DRV2") (pin "A1") (pinfunction "A1_A1") (pintype "bidirectional"))
      (node (ref "SV2") (pin "3") (pinfunction "3_3") (pintype "passive"))
    )
    (net (code "107") (name "Net-(DRV2-PadA2)") (class "Default")
      (node (ref "DRV2") (pin "A2") (pinfunction "A2_A2") (pintype "bidirectional"))
      (node (ref "SV2") (pin "4") (pinfunction "4_4") (pintype "passive"))
    )
    (net (code "108") (name "Net-(DRV2-PadB1)") (class "Default")
      (node (ref "DRV2") (pin "B1") (pinfunction "B1_B1") (pintype "bidirectional"))
      (node (ref "SV2") (pin "2") (pinfunction "2_2") (pintype "passive"))
    )
    (net (code "109") (name "Net-(DRV2-PadB2)") (class "Default")
      (node (ref "DRV2") (pin "B2") (pinfunction "B2_B2") (pintype "bidirectional"))
      (node (ref "SV2") (pin "1") (pinfunction "1_1") (pintype "passive"))
    )
    (net (code "110") (name "Net-(F1-1)") (class "Default")
      (node (ref "F1") (pin "P$1") (pinfunction "1_P$1") (pintype "bidirectional"))
      (node (ref "S1") (pin "3") (pinfunction "3_3") (pintype "bidirectional"))
      (node (ref "SJ1") (pin "1") (pinfunction "1_1") (pintype "passive"))
    )
    (net (code "111") (name "Net-(IC1-B)") (class "Default")
      (node (ref "IC1") (pin "4") (pinfunction "B_4") (pintype "bidirectional"))
      (node (ref "JP1") (pin "2") (pinfunction "2_2") (pintype "passive"))
      (node (ref "PLED1") (pin "3") (pinfunction "DI_3") (pintype "bidirectional"))
    )
    (net (code "112") (name "Net-(IC4-AIN)") (class "Default")
      (node (ref "IC4") (pin "3") (pinfunction "AIN_3") (pintype "bidirectional"))
      (node (ref "R1") (pin "2") (pinfunction "2_2") (pintype "passive"))
      (node (ref "R2") (pin "1") (pinfunction "1_1") (pintype "passive"))
    )
    (net (code "113") (name "Net-(IC5-AIN)") (class "Default")
      (node (ref "IC5") (pin "3") (pinfunction "AIN_3") (pintype "bidirectional"))
      (node (ref "R9") (pin "1") (pinfunction "1_1") (pintype "passive"))
      (node (ref "S2") (pin "5") (pinfunction "COMMON_5") (pintype "bidirectional"))
    )
    (net (code "114") (name "Net-(IC6-P4)") (class "Default")
      (node (ref "D7") (pin "C") (pinfunction "C_C") (pintype "passive"))
      (node (ref "IC6") (pin "9") (pinfunction "P4_9") (pintype "bidirectional"))
    )
    (net (code "115") (name "Net-(IC6-P5)") (class "Default")
      (node (ref "D5") (pin "C") (pinfunction "C_C") (pintype "passive"))
      (node (ref "IC6") (pin "10") (pinfunction "P5_10") (pintype "bidirectional"))
    )
    (net (code "116") (name "Net-(IC6-P6)") (class "Default")
      (node (ref "D6") (pin "C") (pinfunction "C_C") (pintype "passive"))
      (node (ref "IC6") (pin "11") (pinfunction "P6_11") (pintype "bidirectional"))
    )
    (net (code "117") (name "Net-(IC6-P7)") (class "Default")
      (node (ref "D4") (pin "C") (pinfunction "C_C") (pintype "passive"))
      (node (ref "IC6") (pin "12") (pinfunction "P7_12") (pintype "bidirectional"))
    )
    (net (code "118") (name "Net-(IC7-P4)") (class "Default")
      (node (ref "D9") (pin "C") (pinfunction "C_C") (pintype "passive"))
      (node (ref "IC7") (pin "9") (pinfunction "P4_9") (pintype "bidirectional"))
    )
    (net (code "119") (name "Net-(IC7-P5)") (class "Default")
      (node (ref "D11") (pin "C") (pinfunction "C_C") (pintype "passive"))
      (node (ref "IC7") (pin "10") (pinfunction "P5_10") (pintype "bidirectional"))
    )
    (net (code "120") (name "Net-(IC7-P6)") (class "Default")
      (node (ref "D8") (pin "C") (pinfunction "C_C") (pintype "passive"))
      (node (ref "IC7") (pin "11") (pinfunction "P6_11") (pintype "bidirectional"))
    )
    (net (code "121") (name "Net-(IC7-P7)") (class "Default")
      (node (ref "D10") (pin "C") (pinfunction "C_C") (pintype "passive"))
      (node (ref "IC7") (pin "12") (pinfunction "P7_12") (pintype "bidirectional"))
    )
    (net (code "122") (name "Net-(IRLED1-A)") (class "Default")
      (node (ref "IRLED1") (pin "1") (pinfunction "A_1") (pintype "passive"))
      (node (ref "R35") (pin "2") (pinfunction "2_2") (pintype "passive"))
    )
    (net (code "123") (name "Net-(IRLED2-A)") (class "Default")
      (node (ref "IRLED2") (pin "1") (pinfunction "A_1") (pintype "passive"))
      (node (ref "R37") (pin "2") (pinfunction "2_2") (pintype "passive"))
    )
    (net (code "124") (name "Net-(IRLED3-A)") (class "Default")
      (node (ref "IRLED3") (pin "1") (pinfunction "A_1") (pintype "passive"))
      (node (ref "R39") (pin "2") (pinfunction "2_2") (pintype "passive"))
    )
    (net (code "125") (name "Net-(IRLED4-A)") (class "Default")
      (node (ref "IRLED4") (pin "1") (pinfunction "A_1") (pintype "passive"))
      (node (ref "R41") (pin "2") (pinfunction "2_2") (pintype "passive"))
    )
    (net (code "126") (name "Net-(IRLED5-A)") (class "Default")
      (node (ref "IRLED5") (pin "1") (pinfunction "A_1") (pintype "passive"))
      (node (ref "R43") (pin "2") (pinfunction "2_2") (pintype "passive"))
    )
    (net (code "127") (name "Net-(IRLED6-A)") (class "Default")
      (node (ref "IRLED6") (pin "1") (pinfunction "A_1") (pintype "passive"))
      (node (ref "R45") (pin "2") (pinfunction "2_2") (pintype "passive"))
    )
    (net (code "128") (name "Net-(IRLED7-A)") (class "Default")
      (node (ref "IRLED7") (pin "1") (pinfunction "A_1") (pintype "passive"))
      (node (ref "R47") (pin "2") (pinfunction "2_2") (pintype "passive"))
    )
    (net (code "129") (name "Net-(IRLED8-A)") (class "Default")
      (node (ref "IRLED8") (pin "1") (pinfunction "A_1") (pintype "passive"))
      (node (ref "R49") (pin "2") (pinfunction "2_2") (pintype "passive"))
    )
    (net (code "130") (name "Net-(IRLED9-A)") (class "Default")
      (node (ref "IRLED9") (pin "1") (pinfunction "A_1") (pintype "passive"))
      (node (ref "R51") (pin "2") (pinfunction "2_2") (pintype "passive"))
    )
    (net (code "131") (name "Net-(IRLED10-A)") (class "Default")
      (node (ref "IRLED10") (pin "1") (pinfunction "A_1") (pintype "passive"))
      (node (ref "R53") (pin "2") (pinfunction "2_2") (pintype "passive"))
    )
    (net (code "132") (name "Net-(IRLED11-A)") (class "Default")
      (node (ref "IRLED11") (pin "1") (pinfunction "A_1") (pintype "passive"))
      (node (ref "R55") (pin "2") (pinfunction "2_2") (pintype "passive"))
    )
    (net (code "133") (name "Net-(J1-Pad2)") (class "Default")
      (node (ref "J1") (pin "2") (pinfunction "2_2") (pintype "passive"))
      (node (ref "S1") (pin "2") (pinfunction "2_2") (pintype "bidirectional"))
    )
    (net (code "134") (name "Net-(JP18-Pad2)") (class "Default")
      (node (ref "JP18") (pin "2") (pinfunction "2_2") (pintype "passive"))
      (node (ref "JP19") (pin "1") (pinfunction "1_1") (pintype "passive"))
    )
    (net (code "135") (name "Net-(JP22-Pad2)") (class "Default")
      (node (ref "JP22") (pin "2") (pinfunction "2_2") (pintype "passive"))
      (node (ref "JP23") (pin "1") (pinfunction "1_1") (pintype "passive"))
    )
    (net (code "136") (name "Net-(LS1-2)") (class "Default")
      (node (ref "LS1") (pin "-") (pinfunction "2_-") (pintype "passive"))
      (node (ref "Q1") (pin "2") (pinfunction "E_2") (pintype "bidirectional"))
    )
    (net (code "137") (name "Net-(PLED1-DO)") (class "Default")
      (node (ref "PLED1") (pin "1") (pinfunction "DO_1") (pintype "bidirectional"))
      (node (ref "PLED2") (pin "3") (pinfunction "DI_3") (pintype "bidirectional"))
    )
    (net (code "138") (name "Net-(PLED1-VDD)") (class "Default")
      (node (ref "C10") (pin "1") (pinfunction "1_1") (pintype "passive"))
      (node (ref "C11") (pin "1") (pinfunction "1_1") (pintype "passive"))
      (node (ref "C12") (pin "1") (pinfunction "1_1") (pintype "passive"))
      (node (ref "C13") (pin "1") (pinfunction "1_1") (pintype "passive"))
      (node (ref "C14") (pin "1") (pinfunction "1_1") (pintype "passive"))
      (node (ref "C15") (pin "1") (pinfunction "1_1") (pintype "passive"))
      (node (ref "C16") (pin "1") (pinfunction "1_1") (pintype "passive"))
      (node (ref "C17") (pin "1") (pinfunction "1_1") (pintype "passive"))
      (node (ref "C7") (pin "1") (pinfunction "1_1") (pintype "passive"))
      (node (ref "JP2") (pin "1") (pinfunction "1_1") (pintype "passive"))
      (node (ref "PLED1") (pin "4") (pinfunction "VDD_4") (pintype "bidirectional"))
      (node (ref "PLED2") (pin "4") (pinfunction "VDD_4") (pintype "bidirectional"))
      (node (ref "PLED3") (pin "4") (pinfunction "VDD_4") (pintype "bidirectional"))
      (node (ref "PLED4") (pin "4") (pinfunction "VDD_4") (pintype "bidirectional"))
      (node (ref "PLED5") (pin "4") (pinfunction "VDD_4") (pintype "bidirectional"))
      (node (ref "PLED6") (pin "4") (pinfunction "VDD_4") (pintype "bidirectional"))
      (node (ref "PLED7") (pin "4") (pinfunction "VDD_4") (pintype "bidirectional"))
      (node (ref "PLED8") (pin "4") (pinfunction "VDD_4") (pintype "bidirectional"))
      (node (ref "PLED9") (pin "4") (pinfunction "VDD_4") (pintype "bidirectional"))
    )
    (net (code "139") (name "Net-(PLED2-DO)") (class "Default")
      (node (ref "PLED2") (pin "1") (pinfunction "DO_1") (pintype "bidirectional"))
      (node (ref "PLED3") (pin "3") (pinfunction "DI_3") (pintype "bidirectional"))
    )
    (net (code "140") (name "Net-(PLED3-DO)") (class "Default")
      (node (ref "PLED3") (pin "1") (pinfunction "DO_1") (pintype "bidirectional"))
      (node (ref "PLED4") (pin "3") (pinfunction "DI_3") (pintype "bidirectional"))
    )
    (net (code "141") (name "Net-(PLED4-DO)") (class "Default")
      (node (ref "PLED4") (pin "1") (pinfunction "DO_1") (pintype "bidirectional"))
      (node (ref "PLED5") (pin "3") (pinfunction "DI_3") (pintype "bidirectional"))
    )
    (net (code "142") (name "Net-(PLED5-DO)") (class "Default")
      (node (ref "PLED5") (pin "1") (pinfunction "DO_1") (pintype "bidirectional"))
      (node (ref "PLED6") (pin "3") (pinfunction "DI_3") (pintype "bidirectional"))
    )
    (net (code "143") (name "Net-(PLED6-DO)") (class "Default")
      (node (ref "PLED6") (pin "1") (pinfunction "DO_1") (pintype "bidirectional"))
      (node (ref "PLED7") (pin "3") (pinfunction "DI_3") (pintype "bidirectional"))
    )
    (net (code "144") (name "Net-(PLED7-DO)") (class "Default")
      (node (ref "PLED7") (pin "1") (pinfunction "DO_1") (pintype "bidirectional"))
      (node (ref "PLED8") (pin "3") (pinfunction "DI_3") (pintype "bidirectional"))
    )
    (net (code "145") (name "Net-(PLED8-DO)") (class "Default")
      (node (ref "PLED8") (pin "1") (pinfunction "DO_1") (pintype "bidirectional"))
      (node (ref "PLED9") (pin "3") (pinfunction "DI_3") (pintype "bidirectional"))
    )
    (net (code "146") (name "Net-(Q1-B)") (class "Default")
      (node (ref "Q1") (pin "1") (pinfunction "B_1") (pintype "bidirectional"))
      (node (ref "R8") (pin "1") (pinfunction "1_1") (pintype "passive"))
    )
    (net (code "147") (name "Net-(Q2-B)") (class "Default")
      (node (ref "Q2") (pin "1") (pinfunction "B_1") (pintype "bidirectional"))
      (node (ref "R13") (pin "1") (pinfunction "1_1") (pintype "passive"))
    )
    (net (code "148") (name "Net-(Q2-C)") (class "Default")
      (node (ref "JP16") (pin "3") (pinfunction "3_3") (pintype "passive"))
      (node (ref "JP17") (pin "2") (pinfunction "2_2") (pintype "passive"))
      (node (ref "Q2") (pin "3") (pinfunction "C_3") (pintype "bidirectional"))
    )
    (net (code "149") (name "Net-(Q2-E)") (class "Default")
      (node (ref "JP17") (pin "1") (pinfunction "1_1") (pintype "passive"))
      (node (ref "Q2") (pin "2") (pinfunction "E_2") (pintype "bidirectional"))
      (node (ref "R17") (pin "1") (pinfunction "1_1") (pintype "passive"))
      (node (ref "R19") (pin "1") (pinfunction "1_1") (pintype "passive"))
      (node (ref "R21") (pin "1") (pinfunction "1_1") (pintype "passive"))
      (node (ref "R23") (pin "1") (pinfunction "1_1") (pintype "passive"))
      (node (ref "R25") (pin "1") (pinfunction "1_1") (pintype "passive"))
      (node (ref "R27") (pin "1") (pinfunction "1_1") (pintype "passive"))
    )
    (net (code "150") (name "Net-(Q9-B)") (class "Default")
      (node (ref "Q9") (pin "1") (pinfunction "B_1") (pintype "bidirectional"))
      (node (ref "R34") (pin "1") (pinfunction "1_1") (pintype "passive"))
    )
    (net (code "151") (name "Net-(Q9-C)") (class "Default")
      (node (ref "JP20") (pin "3") (pinfunction "3_3") (pintype "passive"))
      (node (ref "JP21") (pin "2") (pinfunction "2_2") (pintype "passive"))
      (node (ref "Q9") (pin "3") (pinfunction "C_3") (pintype "bidirectional"))
    )
    (net (code "152") (name "Net-(Q9-E)") (class "Default")
      (node (ref "JP21") (pin "1") (pinfunction "1_1") (pintype "passive"))
      (node (ref "Q9") (pin "2") (pinfunction "E_2") (pintype "bidirectional"))
      (node (ref "R35") (pin "1") (pinfunction "1_1") (pintype "passive"))
      (node (ref "R37") (pin "1") (pinfunction "1_1") (pintype "passive"))
      (node (ref "R39") (pin "1") (pinfunction "1_1") (pintype "passive"))
      (node (ref "R41") (pin "1") (pinfunction "1_1") (pintype "passive"))
      (node (ref "R43") (pin "1") (pinfunction "1_1") (pintype "passive"))
      (node (ref "R45") (pin "1") (pinfunction "1_1") (pintype "passive"))
      (node (ref "R47") (pin "1") (pinfunction "1_1") (pintype "passive"))
      (node (ref "R49") (pin "1") (pinfunction "1_1") (pintype "passive"))
      (node (ref "R51") (pin "1") (pinfunction "1_1") (pintype "passive"))
      (node (ref "R53") (pin "1") (pinfunction "1_1") (pintype "passive"))
      (node (ref "R55") (pin "1") (pinfunction "1_1") (pintype "passive"))
    )
    (net (code "153") (name "Net-(S2-A)") (class "Default")
      (node (ref "R5") (pin "2") (pinfunction "2_2") (pintype "passive"))
      (node (ref "S2") (pin "1") (pinfunction "A_1") (pintype "bidirectional"))
    )
    (net (code "154") (name "Net-(S2-B)") (class "Default")
      (node (ref "R6") (pin "2") (pinfunction "2_2") (pintype "passive"))
      (node (ref "S2") (pin "4") (pinfunction "B_4") (pintype "bidirectional"))
    )
    (net (code "155") (name "Net-(S2-C)") (class "Default")
      (node (ref "R3") (pin "2") (pinfunction "2_2") (pintype "passive"))
      (node (ref "S2") (pin "3") (pinfunction "C_3") (pintype "bidirectional"))
    )
    (net (code "156") (name "Net-(S2-CENTER)") (class "Default")
      (node (ref "R4") (pin "2") (pinfunction "2_2") (pintype "passive"))
      (node (ref "S2") (pin "2") (pinfunction "CENTER_2") (pintype "bidirectional"))
    )
    (net (code "157") (name "Net-(S2-D)") (class "Default")
      (node (ref "R10") (pin "1") (pinfunction "1_1") (pintype "passive"))
      (node (ref "S2") (pin "6") (pinfunction "D_6") (pintype "bidirectional"))
    )
    (net (code "158") (name "SCL") (class "Default")
      (node (ref "IC4") (pin "5") (pinfunction "SCL_5") (pintype "bidirectional"))
      (node (ref "IC7") (pin "14") (pinfunction "SCL_14") (pintype "bidirectional"))
      (node (ref "JP10") (pin "3") (pinfunction "3_3") (pintype "passive"))
      (node (ref "JP13") (pin "9") (pinfunction "9_9") (pintype "passive"))
      (node (ref "JP5") (pin "2") (pinfunction "2_2") (pintype "passive"))
      (node (ref "SV3") (pin "3") (pinfunction "3_3") (pintype "passive"))
    )
    (net (code "159") (name "SCL*") (class "Default")
      (node (ref "IC5") (pin "5") (pinfunction "SCL_5") (pintype "bidirectional"))
      (node (ref "J4") (pin "10") (pinfunction "10_10") (pintype "passive"))
      (node (ref "JP6") (pin "3") (pinfunction "3_3") (pintype "passive"))
    )
    (net (code "160") (name "SCL_") (class "Default")
      (node (ref "IC6") (pin "14") (pinfunction "SCL_14") (pintype "bidirectional"))
      (node (ref "JP12") (pin "8") (pinfunction "8_8") (pintype "passive"))
      (node (ref "SV4") (pin "3") (pinfunction "3_3") (pintype "passive"))
    )
    (net (code "161") (name "SDA") (class "Default")
      (node (ref "IC4") (pin "4") (pinfunction "SDA_4") (pintype "bidirectional"))
      (node (ref "IC7") (pin "15") (pinfunction "SDA_15") (pintype "bidirectional"))
      (node (ref "JP10") (pin "5") (pinfunction "5_5") (pintype "passive"))
      (node (ref "JP13") (pin "8") (pinfunction "8_8") (pintype "passive"))
      (node (ref "JP5") (pin "1") (pinfunction "1_1") (pintype "passive"))
      (node (ref "SV3") (pin "4") (pinfunction "4_4") (pintype "passive"))
    )
    (net (code "162") (name "SDA*") (class "Default")
      (node (ref "IC5") (pin "4") (pinfunction "SDA_4") (pintype "bidirectional"))
      (node (ref "J4") (pin "9") (pinfunction "9_9") (pintype "passive"))
      (node (ref "JP6") (pin "5") (pinfunction "5_5") (pintype "passive"))
    )
    (net (code "163") (name "SDA_") (class "Default")
      (node (ref "IC6") (pin "15") (pinfunction "SDA_15") (pintype "bidirectional"))
      (node (ref "JP12") (pin "9") (pinfunction "9_9") (pintype "passive"))
      (node (ref "SV4") (pin "4") (pinfunction "4_4") (pintype "passive"))
    )
    (net (code "164") (name "SW0_") (class "Default")
      (node (ref "IC6") (pin "4") (pinfunction "P0_4") (pintype "bidirectional"))
      (node (ref "S3") (pin "1") (pinfunction "1_1") (pintype "bidirectional"))
    )
    (net (code "165") (name "SW1_") (class "Default")
      (node (ref "IC6") (pin "5") (pinfunction "P1_5") (pintype "bidirectional"))
      (node (ref "S4") (pin "1") (pinfunction "1_1") (pintype "bidirectional"))
    )
    (net (code "166") (name "VIN") (class "Default")
      (node (ref "C1") (pin "1") (pinfunction "1_1") (pintype "passive"))
      (node (ref "C3") (pin "2") (pinfunction "2_2") (pintype "bidirectional"))
      (node (ref "C4") (pin "1") (pinfunction "1_1") (pintype "passive"))
      (node (ref "C8") (pin "2") (pinfunction "2_2") (pintype "bidirectional"))
      (node (ref "D2") (pin "A") (pinfunction "A_A") (pintype "passive"))
      (node (ref "DRV1") (pin "VMOT") (pinfunction "VMOT_VMOT") (pintype "bidirectional"))
      (node (ref "DRV2") (pin "VMOT") (pinfunction "VMOT_VMOT") (pintype "bidirectional"))
      (node (ref "F1") (pin "P$2") (pinfunction "2_P$2") (pintype "bidirectional"))
      (node (ref "IC2") (pin "3") (pinfunction "IN_3") (pintype "input"))
      (node (ref "IC3") (pin "3") (pinfunction "IN_3") (pintype "input"))
      (node (ref "J6") (pin "3") (pinfunction "3_3") (pintype "passive"))
      (node (ref "JP13") (pin "4") (pinfunction "4_4") (pintype "passive"))
      (node (ref "JP5") (pin "11") (pinfunction "11_11") (pintype "passive"))
      (node (ref "JP5") (pin "12") (pinfunction "12_12") (pintype "passive"))
      (node (ref "R1") (pin "1") (pinfunction "1_1") (pintype "passive"))
      (node (ref "R7") (pin "1") (pinfunction "1_1") (pintype "passive"))
      (node (ref "SJ1") (pin "2") (pinfunction "2_2") (pintype "passive"))
    )
    (net (code "167") (name "VIN*") (class "Default")
      (node (ref "J2") (pin "8") (pinfunction "8_8") (pintype "passive"))
      (node (ref "JP3") (pin "4") (pinfunction "4_4") (pintype "passive"))
    )
    (net (code "168") (name "VIN_") (class "Default")
      (node (ref "JP12") (pin "13") (pinfunction "13_13") (pintype "passive"))
    )
    (net (code "169") (name "VSELECT") (class "Default")
      (node (ref "DRV1") (pin "FLT") (pinfunction "FLT_FLT") (pintype "bidirectional"))
      (node (ref "DRV2") (pin "FLT") (pinfunction "FLT_FLT") (pintype "bidirectional"))
      (node (ref "IC1") (pin "1") (pinfunction "VCC(A)_1") (pintype "power_in"))
      (node (ref "IC1") (pin "5") (pinfunction "DIR_5") (pintype "input"))
      (node (ref "IC7") (pin "16") (pinfunction "VDD_16") (pintype "bidirectional"))
      (node (ref "JP15") (pin "2") (pinfunction "2_2") (pintype "passive"))
      (node (ref "R30") (pin "1") (pinfunction "1_1") (pintype "passive"))
      (node (ref "R31") (pin "1") (pinfunction "1_1") (pintype "passive"))
      (node (ref "R32") (pin "1") (pinfunction "1_1") (pintype "passive"))
      (node (ref "R33") (pin "1") (pinfunction "1_1") (pintype "passive"))
      (node (ref "U1") (pin "5") (pinfunction "VCC_5") (pintype "power_in"))
      (node (ref "U2") (pin "5") (pinfunction "VCC_5") (pintype "power_in"))
    )
    (net (code "170") (name "VSELECT_") (class "Default")
      (node (ref "JP14") (pin "2") (pinfunction "2_2") (pintype "passive"))
      (node (ref "JP19") (pin "3") (pinfunction "3_3") (pintype "passive"))
      (node (ref "JP23") (pin "3") (pinfunction "3_3") (pintype "passive"))
      (node (ref "U10") (pin "5") (pinfunction "VCC_5") (pintype "power_in"))
      (node (ref "U11") (pin "5") (pinfunction "VCC_5") (pintype "power_in"))
      (node (ref "U12") (pin "5") (pinfunction "VCC_5") (pintype "power_in"))
      (node (ref "U3") (pin "5") (pinfunction "VCC_5") (pintype "power_in"))
      (node (ref "U4") (pin "5") (pinfunction "VCC_5") (pintype "power_in"))
      (node (ref "U5") (pin "5") (pinfunction "VCC_5") (pintype "power_in"))
      (node (ref "U6") (pin "5") (pinfunction "VCC_5") (pintype "power_in"))
      (node (ref "U7") (pin "5") (pinfunction "VCC_5") (pintype "power_in"))
      (node (ref "U8") (pin "5") (pinfunction "VCC_5") (pintype "power_in"))
      (node (ref "U9") (pin "5") (pinfunction "VCC_5") (pintype "power_in"))
    )
    (net (code "171") (name "unconnected-(DRV1-(CONFIG)-PadCONFIG)") (class "Default")
      (node (ref "DRV1") (pin "CONFIG") (pinfunction "(CONFIG)_CONFIG") (pintype "bidirectional"))
    )
    (net (code "172") (name "unconnected-(DRV1-(VREF)-PadVREF)") (class "Default")
      (node (ref "DRV1") (pin "VREF") (pinfunction "(VREF)_VREF") (pintype "bidirectional"))
    )
    (net (code "173") (name "unconnected-(DRV1-PadSLP)") (class "Default")
      (node (ref "DRV1") (pin "SLP") (pinfunction "SLP_SLP") (pintype "bidirectional"))
    )
    (net (code "174") (name "unconnected-(DRV2-(CONFIG)-PadCONFIG)") (class "Default")
      (node (ref "DRV2") (pin "CONFIG") (pinfunction "(CONFIG)_CONFIG") (pintype "bidirectional"))
    )
    (net (code "175") (name "unconnected-(DRV2-(VREF)-PadVREF)") (class "Default")
      (node (ref "DRV2") (pin "VREF") (pinfunction "(VREF)_VREF") (pintype "bidirectional"))
    )
    (net (code "176") (name "unconnected-(DRV2-PadSLP)") (class "Default")
      (node (ref "DRV2") (pin "SLP") (pinfunction "SLP_SLP") (pintype "bidirectional"))
    )
    (net (code "177") (name "unconnected-(IC6-~{INT}-Pad13)") (class "Default")
      (node (ref "IC6") (pin "13") (pinfunction "~{INT}_13") (pintype "bidirectional"))
    )
    (net (code "178") (name "unconnected-(IC7-P3-Pad7)") (class "Default")
      (node (ref "IC7") (pin "7") (pinfunction "P3_7") (pintype "bidirectional"))
    )
    (net (code "179") (name "unconnected-(IC7-~{INT}-Pad13)") (class "Default")
      (node (ref "IC7") (pin "13") (pinfunction "~{INT}_13") (pintype "bidirectional"))
    )
    (net (code "180") (name "unconnected-(J2-Pad1)") (class "Default")
      (node (ref "J2") (pin "1") (pinfunction "1_1") (pintype "passive"))
    )
    (net (code "181") (name "unconnected-(J2-Pad2)") (class "Default")
      (node (ref "J2") (pin "2") (pinfunction "2_2") (pintype "passive"))
    )
    (net (code "182") (name "unconnected-(J2-Pad3)") (class "Default")
      (node (ref "J2") (pin "3") (pinfunction "3_3") (pintype "passive"))
    )
    (net (code "183") (name "unconnected-(J2-Pad4)") (class "Default")
      (node (ref "J2") (pin "4") (pinfunction "4_4") (pintype "passive"))
    )
    (net (code "184") (name "unconnected-(J2-Pad5)") (class "Default")
      (node (ref "J2") (pin "5") (pinfunction "5_5") (pintype "passive"))
    )
    (net (code "185") (name "unconnected-(J4-Pad8)") (class "Default")
      (node (ref "J4") (pin "8") (pinfunction "8_8") (pintype "passive"))
    )
    (net (code "186") (name "unconnected-(JP12-Pad12)") (class "Default")
      (node (ref "JP12") (pin "12") (pinfunction "12_12") (pintype "passive"))
    )
    (net (code "187") (name "unconnected-(JP13-Pad5)") (class "Default")
      (node (ref "JP13") (pin "5") (pinfunction "5_5") (pintype "passive"))
    )
    (net (code "188") (name "unconnected-(PLED9-DO-Pad1)") (class "Default")
      (node (ref "PLED9") (pin "1") (pinfunction "DO_1") (pintype "bidirectional"))
    )
    (net (code "189") (name "unconnected-(S1-Pad1)") (class "Default")
      (node (ref "S1") (pin "1") (pinfunction "1_1") (pintype "bidirectional"))
    )
    (net (code "190") (name "unconnected-(S2-Pad7)") (class "Default")
      (node (ref "S2") (pin "7") (pinfunction "7_7") (pintype "bidirectional"))
    )
    (net (code "191") (name "unconnected-(S2-Pad8)") (class "Default")
      (node (ref "S2") (pin "8") (pinfunction "8_8") (pintype "bidirectional"))
    )
  )
)
